# SCH_ultrasound_version2_2023-05-13.net
KiCad netlist of a schematic drawn in EasyEDA
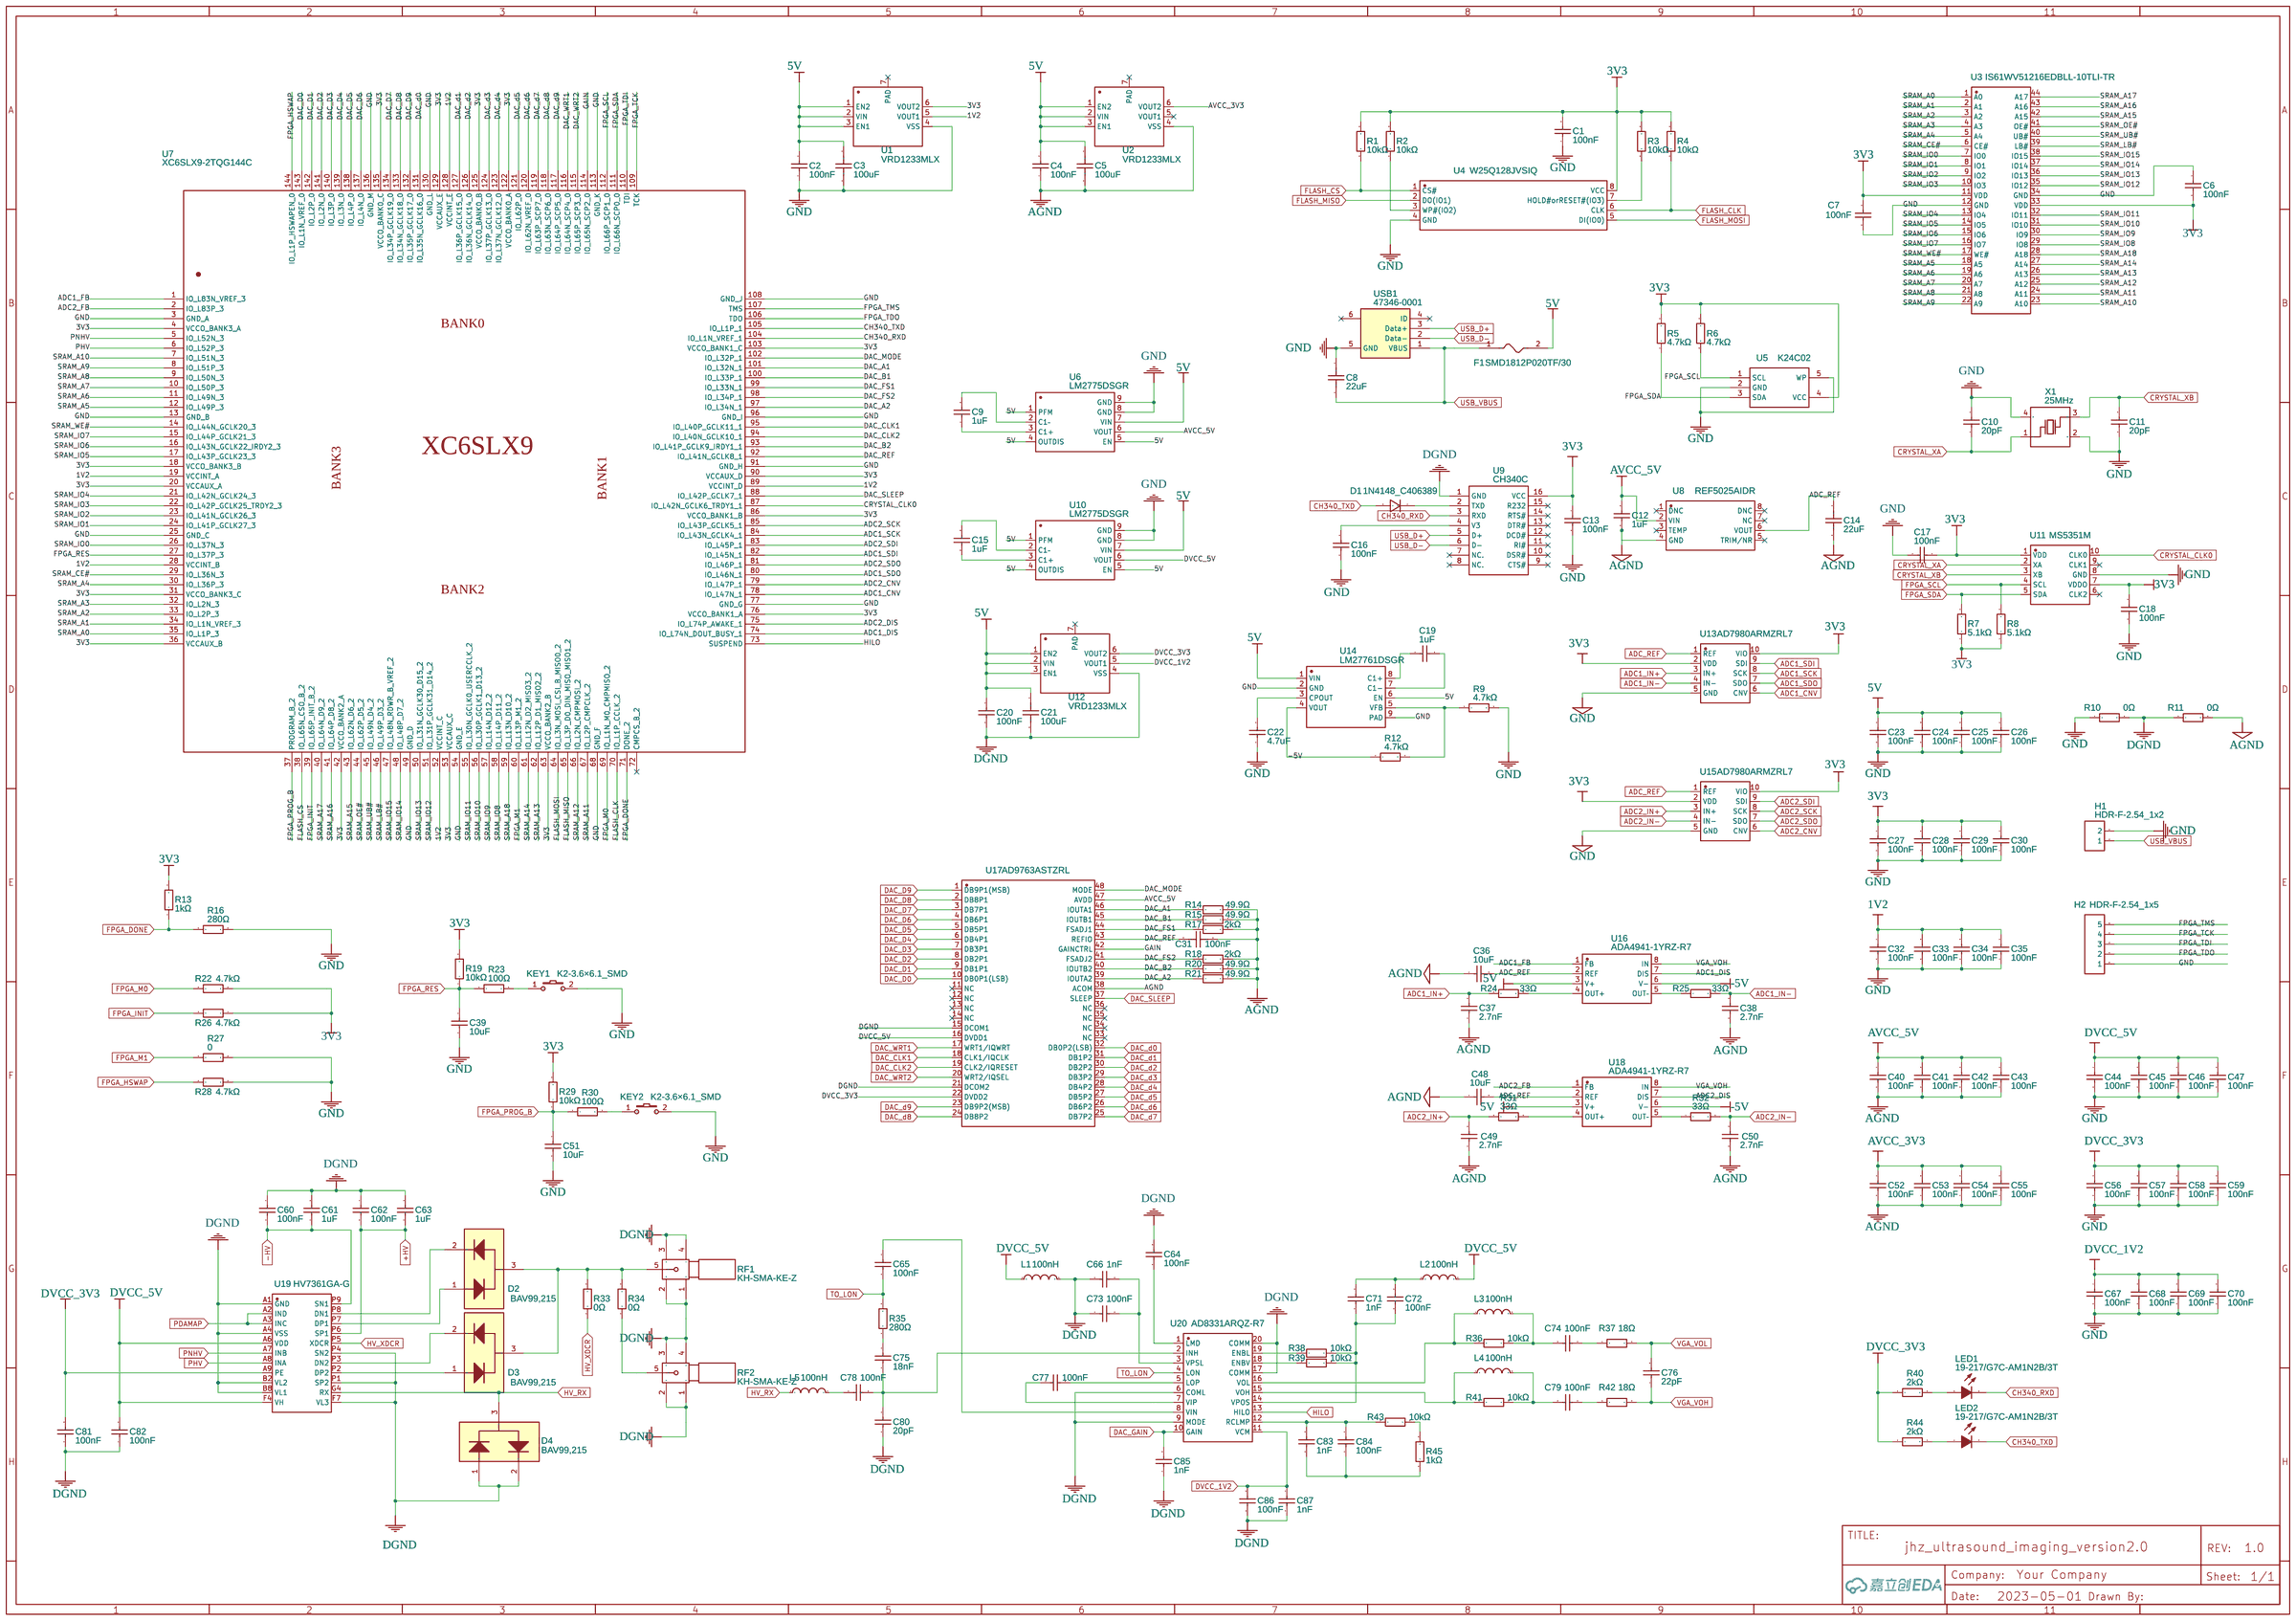
[diagram p0: schematic sheet]

(export (version "E")
  (design (tool "Eeschema 10.0.6"))
  (components
    (comp (ref "C1")
      (value "100nF")
      (fields
        (field (name "BOM_Manufacturer Part") "0603B104K500NT")
        (field (name "BOM_Supplier Part") "C30926")
      )
      (libsource (lib "") (part "0603B104K500NT"))
    )
    (comp (ref "C2")
      (value "100nF")
      (fields
        (field (name "BOM_Manufacturer Part") "0603B104K500NT")
        (field (name "BOM_Supplier Part") "C30926")
      )
      (libsource (lib "") (part "0603B104K500NT"))
    )
    (comp (ref "C3")
      (value "100uF")
      (fields
        (field (name "BOM_Manufacturer Part") "1206X107M6R3NT")
        (field (name "BOM_Supplier Part") "C178304")
      )
      (libsource (lib "") (part "1206X107M6R3NT"))
    )
    (comp (ref "C4")
      (value "100nF")
      (fields
        (field (name "BOM_Manufacturer Part") "0603B104K500NT")
        (field (name "BOM_Supplier Part") "C30926")
      )
      (libsource (lib "") (part "0603B104K500NT"))
    )
    (comp (ref "C5")
      (value "100uF")
      (fields
        (field (name "BOM_Manufacturer Part") "1206X107M6R3NT")
        (field (name "BOM_Supplier Part") "C178304")
      )
      (libsource (lib "") (part "1206X107M6R3NT"))
    )
    (comp (ref "C6")
      (value "100nF")
      (fields
        (field (name "BOM_Manufacturer Part") "0603B104K500NT")
        (field (name "BOM_Supplier Part") "C30926")
      )
      (libsource (lib "") (part "0603B104K500NT_1"))
    )
    (comp (ref "C7")
      (value "100nF")
      (fields
        (field (name "BOM_Manufacturer Part") "0603B104K500NT")
        (field (name "BOM_Supplier Part") "C30926")
      )
      (libsource (lib "") (part "0603B104K500NT"))
    )
    (comp (ref "C8")
      (value "22uF")
      (fields
        (field (name "BOM_Manufacturer Part") "0805X226M160NT")
        (field (name "BOM_Supplier Part") "C129302")
      )
      (libsource (lib "") (part "0805X226M160NT"))
    )
    (comp (ref "C9")
      (value "1uF")
      (fields
        (field (name "BOM_Manufacturer Part") "0603B105K250NT")
        (field (name "BOM_Supplier Part") "C59302")
      )
      (libsource (lib "") (part "0603B105K250NT"))
    )
    (comp (ref "C10")
      (value "20pF")
      (fields
        (field (name "BOM_Manufacturer Part") "0402CG200J500NT")
        (field (name "BOM_Supplier Part") "C1554")
      )
      (libsource (lib "") (part "0402CG200J500NT"))
    )
    (comp (ref "C11")
      (value "20pF")
      (fields
        (field (name "BOM_Manufacturer Part") "0402CG200J500NT")
        (field (name "BOM_Supplier Part") "C1554")
      )
      (libsource (lib "") (part "0402CG200J500NT"))
    )
    (comp (ref "C12")
      (value "1uF")
      (fields
        (field (name "BOM_Manufacturer Part") "0603B105K250NT")
        (field (name "BOM_Supplier Part") "C59302")
      )
      (libsource (lib "") (part "0603B105K250NT"))
    )
    (comp (ref "C13")
      (value "100nF")
      (fields
        (field (name "BOM_Manufacturer Part") "0603B104K500NT")
        (field (name "BOM_Supplier Part") "C30926")
      )
      (libsource (lib "") (part "0603B104K500NT_1"))
    )
    (comp (ref "C14")
      (value "22uF")
      (fields
        (field (name "BOM_Manufacturer Part") "0805X226M160NT")
        (field (name "BOM_Supplier Part") "C129302")
      )
      (libsource (lib "") (part "0805X226M160NT"))
    )
    (comp (ref "C15")
      (value "1uF")
      (fields
        (field (name "BOM_Manufacturer Part") "0603B105K250NT")
        (field (name "BOM_Supplier Part") "C59302")
      )
      (libsource (lib "") (part "0603B105K250NT"))
    )
    (comp (ref "C16")
      (value "100nF")
      (fields
        (field (name "BOM_Manufacturer Part") "0603B104K500NT")
        (field (name "BOM_Supplier Part") "C30926")
      )
      (libsource (lib "") (part "0603B104K500NT_1"))
    )
    (comp (ref "C17")
      (value "100nF")
      (fields
        (field (name "BOM_Manufacturer Part") "0603B104K500NT")
        (field (name "BOM_Supplier Part") "C30926")
      )
      (libsource (lib "") (part "0603B104K500NT_2"))
    )
    (comp (ref "C18")
      (value "100nF")
      (fields
        (field (name "BOM_Manufacturer Part") "0603B104K500NT")
        (field (name "BOM_Supplier Part") "C30926")
      )
      (libsource (lib "") (part "0603B104K500NT"))
    )
    (comp (ref "C19")
      (value "1uF")
      (fields
        (field (name "BOM_Manufacturer Part") "0603B105K250NT")
        (field (name "BOM_Supplier Part") "C59302")
      )
      (libsource (lib "") (part "0603B105K250NT_1"))
    )
    (comp (ref "C20")
      (value "100nF")
      (fields
        (field (name "BOM_Manufacturer Part") "0603B104K500NT")
        (field (name "BOM_Supplier Part") "C30926")
      )
      (libsource (lib "") (part "0603B104K500NT"))
    )
    (comp (ref "C21")
      (value "100uF")
      (fields
        (field (name "BOM_Manufacturer Part") "1206X107M6R3NT")
        (field (name "BOM_Supplier Part") "C178304")
      )
      (libsource (lib "") (part "1206X107M6R3NT"))
    )
    (comp (ref "C22")
      (value "4.7uF")
      (fields
        (field (name "BOM_Manufacturer Part") "1206B475K500NT")
        (field (name "BOM_Supplier Part") "C29823")
      )
      (libsource (lib "") (part "1206B475K500NT"))
    )
    (comp (ref "C23")
      (value "100nF")
      (fields
        (field (name "BOM_Manufacturer Part") "0603B104K500NT")
        (field (name "BOM_Supplier Part") "C30926")
      )
      (libsource (lib "") (part "0603B104K500NT_1"))
    )
    (comp (ref "C24")
      (value "100nF")
      (fields
        (field (name "BOM_Manufacturer Part") "0603B104K500NT")
        (field (name "BOM_Supplier Part") "C30926")
      )
      (libsource (lib "") (part "0603B104K500NT"))
    )
    (comp (ref "C25")
      (value "100nF")
      (fields
        (field (name "BOM_Manufacturer Part") "0603B104K500NT")
        (field (name "BOM_Supplier Part") "C30926")
      )
      (libsource (lib "") (part "0603B104K500NT"))
    )
    (comp (ref "C26")
      (value "100nF")
      (fields
        (field (name "BOM_Manufacturer Part") "0603B104K500NT")
        (field (name "BOM_Supplier Part") "C30926")
      )
      (libsource (lib "") (part "0603B104K500NT"))
    )
    (comp (ref "C27")
      (value "100nF")
      (fields
        (field (name "BOM_Manufacturer Part") "0603B104K500NT")
        (field (name "BOM_Supplier Part") "C30926")
      )
      (libsource (lib "") (part "0603B104K500NT_1"))
    )
    (comp (ref "C28")
      (value "100nF")
      (fields
        (field (name "BOM_Manufacturer Part") "0603B104K500NT")
        (field (name "BOM_Supplier Part") "C30926")
      )
      (libsource (lib "") (part "0603B104K500NT"))
    )
    (comp (ref "C29")
      (value "100nF")
      (fields
        (field (name "BOM_Manufacturer Part") "0603B104K500NT")
        (field (name "BOM_Supplier Part") "C30926")
      )
      (libsource (lib "") (part "0603B104K500NT"))
    )
    (comp (ref "C30")
      (value "100nF")
      (fields
        (field (name "BOM_Manufacturer Part") "0603B104K500NT")
        (field (name "BOM_Supplier Part") "C30926")
      )
      (libsource (lib "") (part "0603B104K500NT"))
    )
    (comp (ref "C31")
      (value "100nF")
      (fields
        (field (name "BOM_Manufacturer Part") "C0603B104K500NT")
        (field (name "BOM_Supplier Part") "C478888")
      )
      (libsource (lib "") (part "C0603B104K500NT"))
    )
    (comp (ref "C32")
      (value "100nF")
      (fields
        (field (name "BOM_Manufacturer Part") "0603B104K500NT")
        (field (name "BOM_Supplier Part") "C30926")
      )
      (libsource (lib "") (part "0603B104K500NT_1"))
    )
    (comp (ref "C33")
      (value "100nF")
      (fields
        (field (name "BOM_Manufacturer Part") "0603B104K500NT")
        (field (name "BOM_Supplier Part") "C30926")
      )
      (libsource (lib "") (part "0603B104K500NT"))
    )
    (comp (ref "C34")
      (value "100nF")
      (fields
        (field (name "BOM_Manufacturer Part") "0603B104K500NT")
        (field (name "BOM_Supplier Part") "C30926")
      )
      (libsource (lib "") (part "0603B104K500NT"))
    )
    (comp (ref "C35")
      (value "100nF")
      (fields
        (field (name "BOM_Manufacturer Part") "0603B104K500NT")
        (field (name "BOM_Supplier Part") "C30926")
      )
      (libsource (lib "") (part "0603B104K500NT"))
    )
    (comp (ref "C36")
      (value "10uF")
      (fields
        (field (name "BOM_Manufacturer Part") "0805X106K250NT")
        (field (name "BOM_Supplier Part") "C40894")
      )
      (libsource (lib "") (part "0805X106K250NT_1"))
    )
    (comp (ref "C37")
      (value "2.7nF")
      (fields
        (field (name "BOM_Manufacturer Part") "0603B272K500NT")
        (field (name "BOM_Supplier Part") "C1609")
      )
      (libsource (lib "") (part "0603B272K500NT"))
    )
    (comp (ref "C38")
      (value "2.7nF")
      (fields
        (field (name "BOM_Manufacturer Part") "0603B272K500NT")
        (field (name "BOM_Supplier Part") "C1609")
      )
      (libsource (lib "") (part "0603B272K500NT"))
    )
    (comp (ref "C39")
      (value "10uF")
      (fields
        (field (name "BOM_Manufacturer Part") "0805X106K250NT")
        (field (name "BOM_Supplier Part") "C40894")
      )
      (libsource (lib "") (part "0805X106K250NT"))
    )
    (comp (ref "C40")
      (value "100nF")
      (fields
        (field (name "BOM_Manufacturer Part") "0603B104K500NT")
        (field (name "BOM_Supplier Part") "C30926")
      )
      (libsource (lib "") (part "0603B104K500NT_1"))
    )
    (comp (ref "C41")
      (value "100nF")
      (fields
        (field (name "BOM_Manufacturer Part") "0603B104K500NT")
        (field (name "BOM_Supplier Part") "C30926")
      )
      (libsource (lib "") (part "0603B104K500NT"))
    )
    (comp (ref "C42")
      (value "100nF")
      (fields
        (field (name "BOM_Manufacturer Part") "0603B104K500NT")
        (field (name "BOM_Supplier Part") "C30926")
      )
      (libsource (lib "") (part "0603B104K500NT"))
    )
    (comp (ref "C43")
      (value "100nF")
      (fields
        (field (name "BOM_Manufacturer Part") "0603B104K500NT")
        (field (name "BOM_Supplier Part") "C30926")
      )
      (libsource (lib "") (part "0603B104K500NT"))
    )
    (comp (ref "C44")
      (value "100nF")
      (fields
        (field (name "BOM_Manufacturer Part") "0603B104K500NT")
        (field (name "BOM_Supplier Part") "C30926")
      )
      (libsource (lib "") (part "0603B104K500NT_1"))
    )
    (comp (ref "C45")
      (value "100nF")
      (fields
        (field (name "BOM_Manufacturer Part") "0603B104K500NT")
        (field (name "BOM_Supplier Part") "C30926")
      )
      (libsource (lib "") (part "0603B104K500NT"))
    )
    (comp (ref "C46")
      (value "100nF")
      (fields
        (field (name "BOM_Manufacturer Part") "0603B104K500NT")
        (field (name "BOM_Supplier Part") "C30926")
      )
      (libsource (lib "") (part "0603B104K500NT"))
    )
    (comp (ref "C47")
      (value "100nF")
      (fields
        (field (name "BOM_Manufacturer Part") "0603B104K500NT")
        (field (name "BOM_Supplier Part") "C30926")
      )
      (libsource (lib "") (part "0603B104K500NT"))
    )
    (comp (ref "C48")
      (value "10uF")
      (fields
        (field (name "BOM_Manufacturer Part") "0805X106K250NT")
        (field (name "BOM_Supplier Part") "C40894")
      )
      (libsource (lib "") (part "0805X106K250NT_1"))
    )
    (comp (ref "C49")
      (value "2.7nF")
      (fields
        (field (name "BOM_Manufacturer Part") "0603B272K500NT")
        (field (name "BOM_Supplier Part") "C1609")
      )
      (libsource (lib "") (part "0603B272K500NT"))
    )
    (comp (ref "C50")
      (value "2.7nF")
      (fields
        (field (name "BOM_Manufacturer Part") "0603B272K500NT")
        (field (name "BOM_Supplier Part") "C1609")
      )
      (libsource (lib "") (part "0603B272K500NT"))
    )
    (comp (ref "C51")
      (value "10uF")
      (fields
        (field (name "BOM_Manufacturer Part") "0805X106K250NT")
        (field (name "BOM_Supplier Part") "C40894")
      )
      (libsource (lib "") (part "0805X106K250NT"))
    )
    (comp (ref "C52")
      (value "100nF")
      (fields
        (field (name "BOM_Manufacturer Part") "0603B104K500NT")
        (field (name "BOM_Supplier Part") "C30926")
      )
      (libsource (lib "") (part "0603B104K500NT_1"))
    )
    (comp (ref "C53")
      (value "100nF")
      (fields
        (field (name "BOM_Manufacturer Part") "0603B104K500NT")
        (field (name "BOM_Supplier Part") "C30926")
      )
      (libsource (lib "") (part "0603B104K500NT"))
    )
    (comp (ref "C54")
      (value "100nF")
      (fields
        (field (name "BOM_Manufacturer Part") "0603B104K500NT")
        (field (name "BOM_Supplier Part") "C30926")
      )
      (libsource (lib "") (part "0603B104K500NT"))
    )
    (comp (ref "C55")
      (value "100nF")
      (fields
        (field (name "BOM_Manufacturer Part") "0603B104K500NT")
        (field (name "BOM_Supplier Part") "C30926")
      )
      (libsource (lib "") (part "0603B104K500NT"))
    )
    (comp (ref "C56")
      (value "100nF")
      (fields
        (field (name "BOM_Manufacturer Part") "0603B104K500NT")
        (field (name "BOM_Supplier Part") "C30926")
      )
      (libsource (lib "") (part "0603B104K500NT_1"))
    )
    (comp (ref "C57")
      (value "100nF")
      (fields
        (field (name "BOM_Manufacturer Part") "0603B104K500NT")
        (field (name "BOM_Supplier Part") "C30926")
      )
      (libsource (lib "") (part "0603B104K500NT"))
    )
    (comp (ref "C58")
      (value "100nF")
      (fields
        (field (name "BOM_Manufacturer Part") "0603B104K500NT")
        (field (name "BOM_Supplier Part") "C30926")
      )
      (libsource (lib "") (part "0603B104K500NT"))
    )
    (comp (ref "C59")
      (value "100nF")
      (fields
        (field (name "BOM_Manufacturer Part") "0603B104K500NT")
        (field (name "BOM_Supplier Part") "C30926")
      )
      (libsource (lib "") (part "0603B104K500NT"))
    )
    (comp (ref "C60")
      (value "100nF")
      (fields
        (field (name "BOM_Manufacturer Part") "0603B104K500NT")
        (field (name "BOM_Supplier Part") "C30926")
      )
      (libsource (lib "") (part "0603B104K500NT_1"))
    )
    (comp (ref "C61")
      (value "1uF")
      (fields
        (field (name "BOM_Manufacturer Part") "0603B105K250NT")
        (field (name "BOM_Supplier Part") "C59302")
      )
      (libsource (lib "") (part "0603B105K250NT"))
    )
    (comp (ref "C62")
      (value "100nF")
      (fields
        (field (name "BOM_Manufacturer Part") "0603B104K500NT")
        (field (name "BOM_Supplier Part") "C30926")
      )
      (libsource (lib "") (part "0603B104K500NT_1"))
    )
    (comp (ref "C63")
      (value "1uF")
      (fields
        (field (name "BOM_Manufacturer Part") "0603B105K250NT")
        (field (name "BOM_Supplier Part") "C59302")
      )
      (libsource (lib "") (part "0603B105K250NT"))
    )
    (comp (ref "C64")
      (value "100nF")
      (fields
        (field (name "BOM_Manufacturer Part") "0603B104K500NT")
        (field (name "BOM_Supplier Part") "C30926")
      )
      (libsource (lib "") (part "0603B104K500NT"))
    )
    (comp (ref "C65")
      (value "100nF")
      (fields
        (field (name "BOM_Manufacturer Part") "0603B104K500NT")
        (field (name "BOM_Supplier Part") "C30926")
      )
      (libsource (lib "") (part "0603B104K500NT"))
    )
    (comp (ref "C66")
      (value "1nF")
      (fields
        (field (name "BOM_Manufacturer Part") "1206B102K202NT")
        (field (name "BOM_Supplier Part") "C9196")
      )
      (libsource (lib "") (part "1206B102K202NT_1"))
    )
    (comp (ref "C67")
      (value "100nF")
      (fields
        (field (name "BOM_Manufacturer Part") "0603B104K500NT")
        (field (name "BOM_Supplier Part") "C30926")
      )
      (libsource (lib "") (part "0603B104K500NT_1"))
    )
    (comp (ref "C68")
      (value "100nF")
      (fields
        (field (name "BOM_Manufacturer Part") "0603B104K500NT")
        (field (name "BOM_Supplier Part") "C30926")
      )
      (libsource (lib "") (part "0603B104K500NT"))
    )
    (comp (ref "C69")
      (value "100nF")
      (fields
        (field (name "BOM_Manufacturer Part") "0603B104K500NT")
        (field (name "BOM_Supplier Part") "C30926")
      )
      (libsource (lib "") (part "0603B104K500NT"))
    )
    (comp (ref "C70")
      (value "100nF")
      (fields
        (field (name "BOM_Manufacturer Part") "0603B104K500NT")
        (field (name "BOM_Supplier Part") "C30926")
      )
      (libsource (lib "") (part "0603B104K500NT"))
    )
    (comp (ref "C71")
      (value "1nF")
      (fields
        (field (name "BOM_Manufacturer Part") "1206B102K202NT")
        (field (name "BOM_Supplier Part") "C9196")
      )
      (libsource (lib "") (part "1206B102K202NT"))
    )
    (comp (ref "C72")
      (value "100nF")
      (fields
        (field (name "BOM_Manufacturer Part") "0603B104K500NT")
        (field (name "BOM_Supplier Part") "C30926")
      )
      (libsource (lib "") (part "0603B104K500NT"))
    )
    (comp (ref "C73")
      (value "100nF")
      (fields
        (field (name "BOM_Manufacturer Part") "0603B104K500NT")
        (field (name "BOM_Supplier Part") "C30926")
      )
      (libsource (lib "") (part "0603B104K500NT_2"))
    )
    (comp (ref "C74")
      (value "100nF")
      (fields
        (field (name "BOM_Manufacturer Part") "0603B104K500NT")
        (field (name "BOM_Supplier Part") "C30926")
      )
      (libsource (lib "") (part "0603B104K500NT_3"))
    )
    (comp (ref "C75")
      (value "18nF")
      (fields
        (field (name "BOM_Manufacturer Part") "0805B183K500NT")
        (field (name "BOM_Supplier Part") "C1723")
      )
      (libsource (lib "") (part "0805B183K500NT"))
    )
    (comp (ref "C76")
      (value "22pF")
      (fields
        (field (name "BOM_Manufacturer Part") "0402CG220J500NT")
        (field (name "BOM_Supplier Part") "C1555")
      )
      (libsource (lib "") (part "0402CG220J500NT"))
    )
    (comp (ref "C77")
      (value "100nF")
      (fields
        (field (name "BOM_Manufacturer Part") "0603B104K500NT")
        (field (name "BOM_Supplier Part") "C30926")
      )
      (libsource (lib "") (part "0603B104K500NT_2"))
    )
    (comp (ref "C78")
      (value "100nF")
      (fields
        (field (name "BOM_Manufacturer Part") "0603B104K500NT")
        (field (name "BOM_Supplier Part") "C30926")
      )
      (libsource (lib "") (part "0603B104K500NT_2"))
    )
    (comp (ref "C79")
      (value "100nF")
      (fields
        (field (name "BOM_Manufacturer Part") "0603B104K500NT")
        (field (name "BOM_Supplier Part") "C30926")
      )
      (libsource (lib "") (part "0603B104K500NT_3"))
    )
    (comp (ref "C80")
      (value "20pF")
      (fields
        (field (name "BOM_Manufacturer Part") "0402CG200J500NT")
        (field (name "BOM_Supplier Part") "C1554")
      )
      (libsource (lib "") (part "0402CG200J500NT"))
    )
    (comp (ref "C81")
      (value "100nF")
      (fields
        (field (name "BOM_Manufacturer Part") "0603B104K500NT")
        (field (name "BOM_Supplier Part") "C30926")
      )
      (libsource (lib "") (part "0603B104K500NT"))
    )
    (comp (ref "C82")
      (value "100nF")
      (fields
        (field (name "BOM_Manufacturer Part") "0603B104K500NT")
        (field (name "BOM_Supplier Part") "C30926")
      )
      (libsource (lib "") (part "0603B104K500NT"))
    )
    (comp (ref "C83")
      (value "1nF")
      (fields
        (field (name "BOM_Manufacturer Part") "1206B102K202NT")
        (field (name "BOM_Supplier Part") "C9196")
      )
      (libsource (lib "") (part "1206B102K202NT"))
    )
    (comp (ref "C84")
      (value "100nF")
      (fields
        (field (name "BOM_Manufacturer Part") "0603B104K500NT")
        (field (name "BOM_Supplier Part") "C30926")
      )
      (libsource (lib "") (part "0603B104K500NT"))
    )
    (comp (ref "C85")
      (value "1nF")
      (fields
        (field (name "BOM_Manufacturer Part") "1206B102K202NT")
        (field (name "BOM_Supplier Part") "C9196")
      )
      (libsource (lib "") (part "1206B102K202NT"))
    )
    (comp (ref "C86")
      (value "100nF")
      (fields
        (field (name "BOM_Manufacturer Part") "0603B104K500NT")
        (field (name "BOM_Supplier Part") "C30926")
      )
      (libsource (lib "") (part "0603B104K500NT_1"))
    )
    (comp (ref "C87")
      (value "1nF")
      (fields
        (field (name "BOM_Manufacturer Part") "1206B102K202NT")
        (field (name "BOM_Supplier Part") "C9196")
      )
      (libsource (lib "") (part "1206B102K202NT_2"))
    )
    (comp (ref "D1")
      (value "1N4148_C406389")
      (fields (field (name "BOM_Manufacturer Part") "1N4148") (field (name "BOM_Supplier Part") "C406389"))
      (libsource (lib "") (part "1N4148_C406389"))
    )
    (comp (ref "D2")
      (value "BAV99,215")
      (fields (field (name "BOM_Supplier Part") "C2500"))
      (libsource (lib "") (part "BAV99,215"))
    )
    (comp (ref "D3")
      (value "BAV99,215")
      (fields (field (name "BOM_Supplier Part") "C2500"))
      (libsource (lib "") (part "BAV99,215"))
    )
    (comp (ref "D4")
      (value "BAV99,215")
      (fields (field (name "BOM_Supplier Part") "C2500"))
      (libsource (lib "") (part "BAV99,215_1"))
    )
    (comp (ref "F1")
      (value "SMD1812P020TF/30")
      (fields (field (name "BOM_Supplier Part") "C13575"))
      (libsource (lib "") (part "SMD1812P020TF/30"))
    )
    (comp (ref "H1")
      (value "HDR-F-2.54_1x2")
      (fields (field (name "BOM_Supplier Part") "C49661"))
      (libsource (lib "") (part "HDR-F-2.54_1x2"))
    )
    (comp (ref "H2")
      (value "HDR-F-2.54_1x5")
      (fields (field (name "BOM_Supplier Part") "C50950"))
      (libsource (lib "") (part "HDR-F-2.54_1x5"))
    )
    (comp (ref "KEY1")
      (value "K2-3.6×6.1_SMD")
      (fields
        (field (name "BOM_Manufacturer Part") "K2-1107ST-A4SW-06")
        (field (name "BOM_Supplier Part") "C118141")
      )
      (libsource (lib "") (part "K2-3.6×6.1_SMD"))
    )
    (comp (ref "KEY2")
      (value "K2-3.6×6.1_SMD")
      (fields
        (field (name "BOM_Manufacturer Part") "K2-1107ST-A4SW-06")
        (field (name "BOM_Supplier Part") "C118141")
      )
      (libsource (lib "") (part "K2-3.6×6.1_SMD"))
    )
    (comp (ref "L1")
      (value "100nH")
      (fields
        (field (name "BOM_Manufacturer Part") "VHF160808HR10JT")
        (field (name "BOM_Supplier Part") "C90214")
      )
      (libsource (lib "") (part "VHF160808HR10JT"))
    )
    (comp (ref "L2")
      (value "100nH")
      (fields
        (field (name "BOM_Manufacturer Part") "VHF160808HR10JT")
        (field (name "BOM_Supplier Part") "C90214")
      )
      (libsource (lib "") (part "VHF160808HR10JT"))
    )
    (comp (ref "L3")
      (value "100nH")
      (fields
        (field (name "BOM_Manufacturer Part") "VHF160808HR10JT")
        (field (name "BOM_Supplier Part") "C90214")
      )
      (libsource (lib "") (part "VHF160808HR10JT"))
    )
    (comp (ref "L4")
      (value "100nH")
      (fields
        (field (name "BOM_Manufacturer Part") "VHF160808HR10JT")
        (field (name "BOM_Supplier Part") "C90214")
      )
      (libsource (lib "") (part "VHF160808HR10JT"))
    )
    (comp (ref "L5")
      (value "100nH")
      (fields
        (field (name "BOM_Manufacturer Part") "VHF160808HR10JT")
        (field (name "BOM_Supplier Part") "C90214")
      )
      (libsource (lib "") (part "VHF160808HR10JT_1"))
    )
    (comp (ref "LED1")
      (value "19-217/G7C-AM1N2B/3T")
      (fields (field (name "BOM_Supplier Part") "C183844"))
      (libsource (lib "") (part "19-217/G7C-AM1N2B/3T"))
    )
    (comp (ref "LED2")
      (value "19-217/G7C-AM1N2B/3T")
      (fields (field (name "BOM_Supplier Part") "C183844"))
      (libsource (lib "") (part "19-217/G7C-AM1N2B/3T"))
    )
    (comp (ref "R1")
      (value "10kΩ")
      (fields
        (field (name "BOM_Manufacturer Part") "RS-03K1002FT")
        (field (name "BOM_Supplier Part") "C115324")
      )
      (libsource (lib "") (part "RS-03K1002FT_1"))
    )
    (comp (ref "R2")
      (value "10kΩ")
      (fields
        (field (name "BOM_Manufacturer Part") "RS-03K1002FT")
        (field (name "BOM_Supplier Part") "C115324")
      )
      (libsource (lib "") (part "RS-03K1002FT_1"))
    )
    (comp (ref "R3")
      (value "10kΩ")
      (fields
        (field (name "BOM_Manufacturer Part") "RS-03K1002FT")
        (field (name "BOM_Supplier Part") "C115324")
      )
      (libsource (lib "") (part "RS-03K1002FT_1"))
    )
    (comp (ref "R4")
      (value "10kΩ")
      (fields
        (field (name "BOM_Manufacturer Part") "RS-03K1002FT")
        (field (name "BOM_Supplier Part") "C115324")
      )
      (libsource (lib "") (part "RS-03K1002FT_1"))
    )
    (comp (ref "R5")
      (value "4.7kΩ")
      (fields
        (field (name "BOM_Manufacturer Part") "RS-03K4701FT")
        (field (name "BOM_Supplier Part") "C116693")
      )
      (libsource (lib "") (part "RS-03K4701FT_2"))
    )
    (comp (ref "R6")
      (value "4.7kΩ")
      (fields
        (field (name "BOM_Manufacturer Part") "RS-03K4701FT")
        (field (name "BOM_Supplier Part") "C116693")
      )
      (libsource (lib "") (part "RS-03K4701FT_2"))
    )
    (comp (ref "R7")
      (value "5.1kΩ")
      (fields
        (field (name "BOM_Manufacturer Part") "RS-03K5101FT")
        (field (name "BOM_Supplier Part") "C156350")
      )
      (libsource (lib "") (part "RS-03K5101FT"))
    )
    (comp (ref "R8")
      (value "5.1kΩ")
      (fields
        (field (name "BOM_Manufacturer Part") "RS-03K5101FT")
        (field (name "BOM_Supplier Part") "C156350")
      )
      (libsource (lib "") (part "RS-03K5101FT"))
    )
    (comp (ref "R9")
      (value "4.7kΩ")
      (fields
        (field (name "BOM_Manufacturer Part") "RS-03K4701FT")
        (field (name "BOM_Supplier Part") "C116693")
      )
      (libsource (lib "") (part "RS-03K4701FT_1"))
    )
    (comp (ref "R10")
      (value "0Ω")
      (fields
        (field (name "BOM_Manufacturer Part") "RS-03000JT")
        (field (name "BOM_Supplier Part") "C115304")
      )
      (libsource (lib "") (part "RS-03000JT_C115304_1"))
    )
    (comp (ref "R11")
      (value "0Ω")
      (fields
        (field (name "BOM_Manufacturer Part") "RS-03000JT")
        (field (name "BOM_Supplier Part") "C115304")
      )
      (libsource (lib "") (part "RS-03000JT_C115304_1"))
    )
    (comp (ref "R12")
      (value "4.7kΩ")
      (fields
        (field (name "BOM_Manufacturer Part") "RS-03K4701FT")
        (field (name "BOM_Supplier Part") "C116693")
      )
      (libsource (lib "") (part "RS-03K4701FT_1"))
    )
    (comp (ref "R13")
      (value "1kΩ")
      (fields
        (field (name "BOM_Manufacturer Part") "RS-03K1001FT")
        (field (name "BOM_Supplier Part") "C115325")
      )
      (libsource (lib "") (part "RS-03K1001FT"))
    )
    (comp (ref "R14")
      (value "49.9Ω")
      (fields
        (field (name "BOM_Manufacturer Part") "RC-02W49R9FT")
        (field (name "BOM_Supplier Part") "C258106")
      )
      (libsource (lib "") (part "RC-02W49R9FT"))
    )
    (comp (ref "R15")
      (value "49.9Ω")
      (fields
        (field (name "BOM_Manufacturer Part") "RC-02W49R9FT")
        (field (name "BOM_Supplier Part") "C258106")
      )
      (libsource (lib "") (part "RC-02W49R9FT"))
    )
    (comp (ref "R16")
      (value "280Ω")
      (fields
        (field (name "BOM_Manufacturer Part") "RC-02W2800FT")
        (field (name "BOM_Supplier Part") "C321421")
      )
      (libsource (lib "") (part "RC-02W2800FT"))
    )
    (comp (ref "R17")
      (value "2kΩ")
      (fields
        (field (name "BOM_Manufacturer Part") "RS-03K2001FT")
        (field (name "BOM_Supplier Part") "C115336")
      )
      (libsource (lib "") (part "RS-03K2001FT"))
    )
    (comp (ref "R18")
      (value "2kΩ")
      (fields
        (field (name "BOM_Manufacturer Part") "RS-03K2001FT")
        (field (name "BOM_Supplier Part") "C115336")
      )
      (libsource (lib "") (part "RS-03K2001FT"))
    )
    (comp (ref "R19")
      (value "10kΩ")
      (fields
        (field (name "BOM_Manufacturer Part") "RS-03K1002FT")
        (field (name "BOM_Supplier Part") "C115324")
      )
      (libsource (lib "") (part "RS-03K1002FT_1"))
    )
    (comp (ref "R20")
      (value "49.9Ω")
      (fields
        (field (name "BOM_Manufacturer Part") "RC-02W49R9FT")
        (field (name "BOM_Supplier Part") "C258106")
      )
      (libsource (lib "") (part "RC-02W49R9FT"))
    )
    (comp (ref "R21")
      (value "49.9Ω")
      (fields
        (field (name "BOM_Manufacturer Part") "RC-02W49R9FT")
        (field (name "BOM_Supplier Part") "C258106")
      )
      (libsource (lib "") (part "RC-02W49R9FT"))
    )
    (comp (ref "R22")
      (value "4.7kΩ")
      (fields
        (field (name "BOM_Manufacturer Part") "RS-03K4701FT")
        (field (name "BOM_Supplier Part") "C116693")
      )
      (libsource (lib "") (part "RS-03K4701FT_1"))
    )
    (comp (ref "R23")
      (value "100Ω")
      (fields
        (field (name "BOM_Manufacturer Part") "RS-03K101JT")
        (field (name "BOM_Supplier Part") "C86983")
      )
      (libsource (lib "") (part "RS-03K101JT"))
    )
    (comp (ref "R24")
      (value "33Ω")
      (fields
        (field (name "BOM_Manufacturer Part") "RC-02W33R0FT")
        (field (name "BOM_Supplier Part") "C140161")
      )
      (libsource (lib "") (part "RC-02W33R0FT"))
    )
    (comp (ref "R25")
      (value "33Ω")
      (fields
        (field (name "BOM_Manufacturer Part") "RC-02W33R0FT")
        (field (name "BOM_Supplier Part") "C140161")
      )
      (libsource (lib "") (part "RC-02W33R0FT"))
    )
    (comp (ref "R26")
      (value "4.7kΩ")
      (fields
        (field (name "BOM_Manufacturer Part") "RS-03K4701FT")
        (field (name "BOM_Supplier Part") "C116693")
      )
      (libsource (lib "") (part "RS-03K4701FT"))
    )
    (comp (ref "R27")
      (value "0")
      (fields (field (name "BOM_Manufacturer Part") "RS-03000JT") (field (name "BOM_Supplier Part") "C73810"))
      (libsource (lib "") (part "RS-03000JT"))
    )
    (comp (ref "R28")
      (value "4.7kΩ")
      (fields
        (field (name "BOM_Manufacturer Part") "RS-03K4701FT")
        (field (name "BOM_Supplier Part") "C116693")
      )
      (libsource (lib "") (part "RS-03K4701FT"))
    )
    (comp (ref "R29")
      (value "10kΩ")
      (fields
        (field (name "BOM_Manufacturer Part") "RS-03K1002FT")
        (field (name "BOM_Supplier Part") "C115324")
      )
      (libsource (lib "") (part "RS-03K1002FT_1"))
    )
    (comp (ref "R30")
      (value "100Ω")
      (fields
        (field (name "BOM_Manufacturer Part") "RS-03K101JT")
        (field (name "BOM_Supplier Part") "C86983")
      )
      (libsource (lib "") (part "RS-03K101JT"))
    )
    (comp (ref "R31")
      (value "33Ω")
      (fields
        (field (name "BOM_Manufacturer Part") "RC-02W33R0FT")
        (field (name "BOM_Supplier Part") "C140161")
      )
      (libsource (lib "") (part "RC-02W33R0FT"))
    )
    (comp (ref "R32")
      (value "33Ω")
      (fields
        (field (name "BOM_Manufacturer Part") "RC-02W33R0FT")
        (field (name "BOM_Supplier Part") "C140161")
      )
      (libsource (lib "") (part "RC-02W33R0FT"))
    )
    (comp (ref "R33")
      (value "0Ω")
      (fields
        (field (name "BOM_Manufacturer Part") "RS-03000JT")
        (field (name "BOM_Supplier Part") "C115304")
      )
      (libsource (lib "") (part "RS-03000JT_C115304"))
    )
    (comp (ref "R34")
      (value "0Ω")
      (fields
        (field (name "BOM_Manufacturer Part") "RS-03000JT")
        (field (name "BOM_Supplier Part") "C115304")
      )
      (libsource (lib "") (part "RS-03000JT_C115304"))
    )
    (comp (ref "R35")
      (value "280Ω")
      (fields
        (field (name "BOM_Manufacturer Part") "RC-02W2800FT")
        (field (name "BOM_Supplier Part") "C321421")
      )
      (libsource (lib "") (part "RC-02W2800FT_1"))
    )
    (comp (ref "R36")
      (value "10kΩ")
      (fields
        (field (name "BOM_Manufacturer Part") "RS-03K1002FT")
        (field (name "BOM_Supplier Part") "C115324")
      )
      (libsource (lib "") (part "RS-03K1002FT"))
    )
    (comp (ref "R37")
      (value "18Ω")
      (fields
        (field (name "BOM_Manufacturer Part") "RS-03K180JT")
        (field (name "BOM_Supplier Part") "C286576")
      )
      (libsource (lib "") (part "RS-03K180JT"))
    )
    (comp (ref "R38")
      (value "10kΩ")
      (fields
        (field (name "BOM_Manufacturer Part") "RS-03K1002FT")
        (field (name "BOM_Supplier Part") "C115324")
      )
      (libsource (lib "") (part "RS-03K1002FT"))
    )
    (comp (ref "R39")
      (value "10kΩ")
      (fields
        (field (name "BOM_Manufacturer Part") "RS-03K1002FT")
        (field (name "BOM_Supplier Part") "C115324")
      )
      (libsource (lib "") (part "RS-03K1002FT"))
    )
    (comp (ref "R40")
      (value "2kΩ")
      (fields
        (field (name "BOM_Manufacturer Part") "RS-03K2001FT")
        (field (name "BOM_Supplier Part") "C115336")
      )
      (libsource (lib "") (part "RS-03K2001FT"))
    )
    (comp (ref "R41")
      (value "10kΩ")
      (fields
        (field (name "BOM_Manufacturer Part") "RS-03K1002FT")
        (field (name "BOM_Supplier Part") "C115324")
      )
      (libsource (lib "") (part "RS-03K1002FT"))
    )
    (comp (ref "R42")
      (value "18Ω")
      (fields
        (field (name "BOM_Manufacturer Part") "RS-03K180JT")
        (field (name "BOM_Supplier Part") "C286576")
      )
      (libsource (lib "") (part "RS-03K180JT"))
    )
    (comp (ref "R43")
      (value "10kΩ")
      (fields
        (field (name "BOM_Manufacturer Part") "RS-03K1002FT")
        (field (name "BOM_Supplier Part") "C115324")
      )
      (libsource (lib "") (part "RS-03K1002FT"))
    )
    (comp (ref "R44")
      (value "2kΩ")
      (fields
        (field (name "BOM_Manufacturer Part") "RS-03K2001FT")
        (field (name "BOM_Supplier Part") "C115336")
      )
      (libsource (lib "") (part "RS-03K2001FT"))
    )
    (comp (ref "R45")
      (value "1kΩ")
      (fields
        (field (name "BOM_Manufacturer Part") "RS-03K1001FT")
        (field (name "BOM_Supplier Part") "C115325")
      )
      (libsource (lib "") (part "RS-03K1001FT"))
    )
    (comp (ref "RF1")
      (value "KH-SMA-KE-Z")
      (fields (field (name "BOM_Supplier Part") "C504007"))
      (libsource (lib "") (part "KH-SMA-KE-Z"))
    )
    (comp (ref "RF2")
      (value "KH-SMA-KE-Z")
      (fields (field (name "BOM_Supplier Part") "C504007"))
      (libsource (lib "") (part "KH-SMA-KE-Z"))
    )
    (comp (ref "U1")
      (value "VRD1233MLX")
      (fields (field (name "BOM_Supplier Part") "C697903"))
      (libsource (lib "") (part "VRD1233MLX"))
    )
    (comp (ref "U2")
      (value "VRD1233MLX")
      (fields (field (name "BOM_Supplier Part") "C697903"))
      (libsource (lib "") (part "VRD1233MLX"))
    )
    (comp (ref "U3")
      (value "IS61WV51216EDBLL-10TLI-TR")
      (fields (field (name "BOM_Supplier Part") "C2065273"))
      (libsource (lib "") (part "IS61WV51216EDBLL-10TLI-TR"))
    )
    (comp (ref "U4")
      (value "W25Q128JVSIQ")
      (fields (field (name "BOM_Supplier Part") "C113767"))
      (libsource (lib "") (part "W25Q128JVSIQ"))
    )
    (comp (ref "U5")
      (value "K24C02")
      (fields (field (name "BOM_Supplier Part") "C84964"))
      (libsource (lib "") (part "K24C02"))
    )
    (comp (ref "U6")
      (value "LM2775DSGR")
      (fields (field (name "BOM_Supplier Part") "C473361"))
      (libsource (lib "") (part "LM2775DSGR"))
    )
    (comp (ref "U7")
      (value "XC6SLX9-2TQG144C")
      (fields (field (name "BOM_Supplier Part") "C27408"))
      (libsource (lib "") (part "XC6SLX9-2TQG144C"))
    )
    (comp (ref "U8")
      (value "REF5025AIDR")
      (fields (field (name "BOM_Supplier Part") "C11341"))
      (libsource (lib "") (part "REF5025AIDR"))
    )
    (comp (ref "U9")
      (value "CH340C")
      (fields (field (name "BOM_Supplier Part") "C84681"))
      (libsource (lib "") (part "CH340C"))
    )
    (comp (ref "U10")
      (value "LM2775DSGR")
      (fields (field (name "BOM_Supplier Part") "C473361"))
      (libsource (lib "") (part "LM2775DSGR"))
    )
    (comp (ref "U11")
      (value "MS5351M")
      (fields (field (name "BOM_Supplier Part") "C1509083"))
      (libsource (lib "") (part "MS5351M"))
    )
    (comp (ref "U12")
      (value "VRD1233MLX")
      (fields (field (name "BOM_Supplier Part") "C697903"))
      (libsource (lib "") (part "VRD1233MLX"))
    )
    (comp (ref "U13")
      (value "AD7980ARMZRL7")
      (fields (field (name "BOM_Supplier Part") "C578576"))
      (libsource (lib "") (part "AD7980ARMZRL7"))
    )
    (comp (ref "U14")
      (value "LM27761DSGR")
      (fields (field (name "BOM_Supplier Part") "C129351"))
      (libsource (lib "") (part "LM27761DSGR"))
    )
    (comp (ref "U15")
      (value "AD7980ARMZRL7")
      (fields (field (name "BOM_Supplier Part") "C578576"))
      (libsource (lib "") (part "AD7980ARMZRL7"))
    )
    (comp (ref "U16")
      (value "ADA4941-1YRZ-R7")
      (fields (field (name "BOM_Supplier Part") "C495334"))
      (libsource (lib "") (part "ADA4941-1YRZ-R7"))
    )
    (comp (ref "U17")
      (value "AD9763ASTZRL")
      (fields (field (name "BOM_Supplier Part") "C481891"))
      (libsource (lib "") (part "AD9763ASTZRL"))
    )
    (comp (ref "U18")
      (value "ADA4941-1YRZ-R7")
      (fields (field (name "BOM_Supplier Part") "C495334"))
      (libsource (lib "") (part "ADA4941-1YRZ-R7"))
    )
    (comp (ref "U19")
      (value "HV7361GA-G")
      (fields (field (name "BOM_Supplier Part") "C633420"))
      (libsource (lib "") (part "HV7361GA-G"))
    )
    (comp (ref "U20")
      (value "AD8331ARQZ-R7")
      (fields (field (name "BOM_Supplier Part") "C578697"))
      (libsource (lib "") (part "AD8331ARQZ-R7"))
    )
    (comp (ref "USB1")
      (value "47346-0001")
      (fields (field (name "BOM_Manufacturer Part") "473460001") (field (name "BOM_Supplier Part") "C132560"))
      (libsource (lib "") (part "47346-0001"))
    )
    (comp (ref "X1")
      (value "25MHz")
      (fields
        (field (name "BOM_Manufacturer Part") "X322525MOB4SI")
        (field (name "BOM_Supplier Part") "C9006")
      )
      (libsource (lib "") (part "X322525MOB4SI"))
    )
  )
  (nets
    (net (code "1") (name "+HV") (class "Default")
      (node (ref "C62") (pin "2") (pinfunction "2_2") (pintype "input"))
      (node (ref "C63") (pin "1") (pinfunction "1_1") (pintype "input"))
      (node (ref "U19") (pin "P6") (pinfunction "SP1_P6") (pintype "unspecified"))
    )
    (net (code "2") (name "-5V") (class "Default")
      (node (ref "R12") (pin "1") (pinfunction "1_1") (pintype "unspecified"))
      (node (ref "U14") (pin "4") (pinfunction "VOUT_4") (pintype "unspecified"))
      (node (ref "U16") (pin "6") (pinfunction "V-_6") (pintype "unspecified"))
      (node (ref "U18") (pin "6") (pinfunction "V-_6") (pintype "unspecified"))
    )
    (net (code "3") (name "-HV") (class "Default")
      (node (ref "C60") (pin "2") (pinfunction "2_2") (pintype "input"))
      (node (ref "C61") (pin "1") (pinfunction "1_1") (pintype "input"))
      (node (ref "U19") (pin "P9") (pinfunction "SN1_P9") (pintype "unspecified"))
    )
    (net (code "4") (name "/ADC1_DIS") (class "Default")
      (node (ref "U16") (pin "7") (pinfunction "DIS_7") (pintype "unspecified"))
      (node (ref "U7") (pin "74") (pinfunction "IO_L74N_DOUT_BUSY_1_74") (pintype "unspecified"))
    )
    (net (code "5") (name "/ADC1_FB") (class "Default")
      (node (ref "U16") (pin "1") (pinfunction "FB_1") (pintype "unspecified"))
      (node (ref "U7") (pin "1") (pinfunction "IO_L83N_VREF_3_1") (pintype "unspecified"))
    )
    (net (code "6") (name "/ADC2_DIS") (class "Default")
      (node (ref "U18") (pin "7") (pinfunction "DIS_7") (pintype "unspecified"))
      (node (ref "U7") (pin "75") (pinfunction "IO_L74P_AWAKE_1_75") (pintype "unspecified"))
    )
    (net (code "7") (name "/ADC2_FB") (class "Default")
      (node (ref "U18") (pin "1") (pinfunction "FB_1") (pintype "unspecified"))
      (node (ref "U7") (pin "2") (pinfunction "IO_L83P_3_2") (pintype "unspecified"))
    )
    (net (code "8") (name "/DAC_A1") (class "Default")
      (node (ref "R14") (pin "1") (pinfunction "1_1") (pintype "unspecified"))
      (node (ref "U17") (pin "46") (pinfunction "IOUTA1_46") (pintype "unspecified"))
      (node (ref "U7") (pin "101") (pinfunction "IO_L32N_1_101") (pintype "unspecified"))
    )
    (net (code "9") (name "/DAC_A2") (class "Default")
      (node (ref "R21") (pin "1") (pinfunction "1_1") (pintype "unspecified"))
      (node (ref "U17") (pin "39") (pinfunction "IOUTA2_39") (pintype "unspecified"))
      (node (ref "U7") (pin "97") (pinfunction "IO_L34N_1_97") (pintype "unspecified"))
    )
    (net (code "10") (name "/DAC_B1") (class "Default")
      (node (ref "R15") (pin "1") (pinfunction "1_1") (pintype "unspecified"))
      (node (ref "U17") (pin "45") (pinfunction "IOUTB1_45") (pintype "unspecified"))
      (node (ref "U7") (pin "100") (pinfunction "IO_L33P_1_100") (pintype "unspecified"))
    )
    (net (code "11") (name "/DAC_B2") (class "Default")
      (node (ref "R20") (pin "1") (pinfunction "1_1") (pintype "unspecified"))
      (node (ref "U17") (pin "40") (pinfunction "IOUTB2_40") (pintype "unspecified"))
      (node (ref "U7") (pin "93") (pinfunction "IO_L41P_GCLK9_IRDY1_1_93") (pintype "unspecified"))
    )
    (net (code "12") (name "/DAC_FS1") (class "Default")
      (node (ref "R17") (pin "1") (pinfunction "1_1") (pintype "input"))
      (node (ref "U17") (pin "44") (pinfunction "FSADJ1_44") (pintype "unspecified"))
      (node (ref "U7") (pin "99") (pinfunction "IO_L33N_1_99") (pintype "unspecified"))
    )
    (net (code "13") (name "/DAC_FS2") (class "Default")
      (node (ref "R18") (pin "1") (pinfunction "1_1") (pintype "input"))
      (node (ref "U17") (pin "41") (pinfunction "FSADJ2_41") (pintype "unspecified"))
      (node (ref "U7") (pin "98") (pinfunction "IO_L34P_1_98") (pintype "unspecified"))
    )
    (net (code "14") (name "/DAC_MODE") (class "Default")
      (node (ref "U17") (pin "48") (pinfunction "MODE_48") (pintype "unspecified"))
      (node (ref "U7") (pin "102") (pinfunction "IO_L32P_1_102") (pintype "unspecified"))
    )
    (net (code "15") (name "/DAC_REF") (class "Default")
      (node (ref "C31") (pin "1") (pinfunction "1_1") (pintype "unspecified"))
      (node (ref "U17") (pin "43") (pinfunction "REFIO_43") (pintype "unspecified"))
      (node (ref "U7") (pin "92") (pinfunction "IO_L41N_GCLK8_1_92") (pintype "unspecified"))
    )
    (net (code "16") (name "/FPGA_TCK") (class "Default")
      (node (ref "H2") (pin "4") (pinfunction "4_4") (pintype "unspecified"))
      (node (ref "U7") (pin "109") (pinfunction "TCK_109") (pintype "unspecified"))
    )
    (net (code "17") (name "/FPGA_TDI") (class "Default")
      (node (ref "H2") (pin "3") (pinfunction "3_3") (pintype "unspecified"))
      (node (ref "U7") (pin "110") (pinfunction "TDI_110") (pintype "unspecified"))
    )
    (net (code "18") (name "/FPGA_TDO") (class "Default")
      (node (ref "H2") (pin "2") (pinfunction "2_2") (pintype "unspecified"))
      (node (ref "U7") (pin "106") (pinfunction "TDO_106") (pintype "unspecified"))
    )
    (net (code "19") (name "/FPGA_TMS") (class "Default")
      (node (ref "H2") (pin "5") (pinfunction "5_5") (pintype "unspecified"))
      (node (ref "U7") (pin "107") (pinfunction "TMS_107") (pintype "unspecified"))
    )
    (net (code "20") (name "/GAIN") (class "Default")
      (node (ref "U17") (pin "42") (pinfunction "GAINCTRL_42") (pintype "unspecified"))
      (node (ref "U7") (pin "114") (pinfunction "IO_L65N_SCP2_0_114") (pintype "unspecified"))
    )
    (net (code "21") (name "/SRAM_A0") (class "Default")
      (node (ref "U3") (pin "1") (pinfunction "A0_1") (pintype "unspecified"))
      (node (ref "U7") (pin "35") (pinfunction "IO_L1P_3_35") (pintype "unspecified"))
    )
    (net (code "22") (name "/SRAM_A1") (class "Default")
      (node (ref "U3") (pin "2") (pinfunction "A1_2") (pintype "unspecified"))
      (node (ref "U7") (pin "34") (pinfunction "IO_L1N_VREF_3_34") (pintype "unspecified"))
    )
    (net (code "23") (name "/SRAM_A2") (class "Default")
      (node (ref "U3") (pin "3") (pinfunction "A2_3") (pintype "unspecified"))
      (node (ref "U7") (pin "33") (pinfunction "IO_L2P_3_33") (pintype "unspecified"))
    )
    (net (code "24") (name "/SRAM_A3") (class "Default")
      (node (ref "U3") (pin "4") (pinfunction "A3_4") (pintype "unspecified"))
      (node (ref "U7") (pin "32") (pinfunction "IO_L2N_3_32") (pintype "unspecified"))
    )
    (net (code "25") (name "/SRAM_A4") (class "Default")
      (node (ref "U3") (pin "5") (pinfunction "A4_5") (pintype "unspecified"))
      (node (ref "U7") (pin "30") (pinfunction "IO_L36P_3_30") (pintype "unspecified"))
    )
    (net (code "26") (name "/SRAM_A5") (class "Default")
      (node (ref "U3") (pin "18") (pinfunction "A5_18") (pintype "unspecified"))
      (node (ref "U7") (pin "12") (pinfunction "IO_L49P_3_12") (pintype "unspecified"))
    )
    (net (code "27") (name "/SRAM_A6") (class "Default")
      (node (ref "U3") (pin "19") (pinfunction "A6_19") (pintype "unspecified"))
      (node (ref "U7") (pin "11") (pinfunction "IO_L49N_3_11") (pintype "unspecified"))
    )
    (net (code "28") (name "/SRAM_A7") (class "Default")
      (node (ref "U3") (pin "20") (pinfunction "A7_20") (pintype "unspecified"))
      (node (ref "U7") (pin "10") (pinfunction "IO_L50P_3_10") (pintype "unspecified"))
    )
    (net (code "29") (name "/SRAM_A8") (class "Default")
      (node (ref "U3") (pin "21") (pinfunction "A8_21") (pintype "unspecified"))
      (node (ref "U7") (pin "9") (pinfunction "IO_L50N_3_9") (pintype "unspecified"))
    )
    (net (code "30") (name "/SRAM_A9") (class "Default")
      (node (ref "U3") (pin "22") (pinfunction "A9_22") (pintype "unspecified"))
      (node (ref "U7") (pin "8") (pinfunction "IO_L51P_3_8") (pintype "unspecified"))
    )
    (net (code "31") (name "/SRAM_A10") (class "Default")
      (node (ref "U3") (pin "23") (pinfunction "A10_23") (pintype "unspecified"))
      (node (ref "U7") (pin "7") (pinfunction "IO_L51N_3_7") (pintype "unspecified"))
    )
    (net (code "32") (name "/SRAM_A11") (class "Default")
      (node (ref "U3") (pin "24") (pinfunction "A11_24") (pintype "unspecified"))
      (node (ref "U7") (pin "67") (pinfunction "IO_L2P_CMPCLK_2_67") (pintype "unspecified"))
    )
    (net (code "33") (name "/SRAM_A12") (class "Default")
      (node (ref "U3") (pin "25") (pinfunction "A12_25") (pintype "unspecified"))
      (node (ref "U7") (pin "66") (pinfunction "IO_L2N_CMPMOSI_2_66") (pintype "unspecified"))
    )
    (net (code "34") (name "/SRAM_A13") (class "Default")
      (node (ref "U3") (pin "26") (pinfunction "A13_26") (pintype "unspecified"))
      (node (ref "U7") (pin "62") (pinfunction "IO_L12P_D1_MISO2_2_62") (pintype "unspecified"))
    )
    (net (code "35") (name "/SRAM_A14") (class "Default")
      (node (ref "U3") (pin "27") (pinfunction "A14_27") (pintype "unspecified"))
      (node (ref "U7") (pin "61") (pinfunction "IO_L12N_D2_MISO3_2_61") (pintype "unspecified"))
    )
    (net (code "36") (name "/SRAM_A15") (class "Default")
      (node (ref "U3") (pin "42") (pinfunction "A15_42") (pintype "unspecified"))
      (node (ref "U7") (pin "43") (pinfunction "IO_L62N_D6_2_43") (pintype "unspecified"))
    )
    (net (code "37") (name "/SRAM_A16") (class "Default")
      (node (ref "U3") (pin "43") (pinfunction "A16_43") (pintype "unspecified"))
      (node (ref "U7") (pin "41") (pinfunction "IO_L64P_D8_2_41") (pintype "unspecified"))
    )
    (net (code "38") (name "/SRAM_A17") (class "Default")
      (node (ref "U3") (pin "44") (pinfunction "A17_44") (pintype "unspecified"))
      (node (ref "U7") (pin "40") (pinfunction "IO_L64N_D9_2_40") (pintype "unspecified"))
    )
    (net (code "39") (name "/SRAM_A18") (class "Default")
      (node (ref "U3") (pin "28") (pinfunction "A18_28") (pintype "unspecified"))
      (node (ref "U7") (pin "59") (pinfunction "IO_L13N_D10_2_59") (pintype "unspecified"))
    )
    (net (code "40") (name "/SRAM_CE#") (class "Default")
      (node (ref "U3") (pin "6") (pinfunction "CE#_6") (pintype "unspecified"))
      (node (ref "U7") (pin "29") (pinfunction "IO_L36N_3_29") (pintype "unspecified"))
    )
    (net (code "41") (name "/SRAM_IO0") (class "Default")
      (node (ref "U3") (pin "7") (pinfunction "IO0_7") (pintype "unspecified"))
      (node (ref "U7") (pin "26") (pinfunction "IO_L37N_3_26") (pintype "unspecified"))
    )
    (net (code "42") (name "/SRAM_IO1") (class "Default")
      (node (ref "U3") (pin "8") (pinfunction "IO1_8") (pintype "unspecified"))
      (node (ref "U7") (pin "24") (pinfunction "IO_L41P_GCLK27_3_24") (pintype "unspecified"))
    )
    (net (code "43") (name "/SRAM_IO2") (class "Default")
      (node (ref "U3") (pin "9") (pinfunction "IO2_9") (pintype "unspecified"))
      (node (ref "U7") (pin "23") (pinfunction "IO_L41N_GCLK26_3_23") (pintype "unspecified"))
    )
    (net (code "44") (name "/SRAM_IO3") (class "Default")
      (node (ref "U3") (pin "10") (pinfunction "IO3_10") (pintype "unspecified"))
      (node (ref "U7") (pin "22") (pinfunction "IO_L42P_GCLK25_TRDY2_3_22") (pintype "unspecified"))
    )
    (net (code "45") (name "/SRAM_IO4") (class "Default")
      (node (ref "U3") (pin "13") (pinfunction "IO4_13") (pintype "unspecified"))
      (node (ref "U7") (pin "21") (pinfunction "IO_L42N_GCLK24_3_21") (pintype "unspecified"))
    )
    (net (code "46") (name "/SRAM_IO5") (class "Default")
      (node (ref "U3") (pin "14") (pinfunction "IO5_14") (pintype "unspecified"))
      (node (ref "U7") (pin "17") (pinfunction "IO_L43P_GCLK23_3_17") (pintype "unspecified"))
    )
    (net (code "47") (name "/SRAM_IO6") (class "Default")
      (node (ref "U3") (pin "15") (pinfunction "IO6_15") (pintype "unspecified"))
      (node (ref "U7") (pin "16") (pinfunction "IO_L43N_GCLK22_IRDY2_3_16") (pintype "unspecified"))
    )
    (net (code "48") (name "/SRAM_IO7") (class "Default")
      (node (ref "U3") (pin "16") (pinfunction "IO7_16") (pintype "unspecified"))
      (node (ref "U7") (pin "15") (pinfunction "IO_L44P_GCLK21_3_15") (pintype "unspecified"))
    )
    (net (code "49") (name "/SRAM_IO8") (class "Default")
      (node (ref "U3") (pin "29") (pinfunction "IO8_29") (pintype "unspecified"))
      (node (ref "U7") (pin "58") (pinfunction "IO_L14P_D11_2_58") (pintype "unspecified"))
    )
    (net (code "50") (name "/SRAM_IO9") (class "Default")
      (node (ref "U3") (pin "30") (pinfunction "IO9_30") (pintype "unspecified"))
      (node (ref "U7") (pin "57") (pinfunction "IO_L14N_D12_2_57") (pintype "unspecified"))
    )
    (net (code "51") (name "/SRAM_IO10") (class "Default")
      (node (ref "U3") (pin "31") (pinfunction "IO10_31") (pintype "unspecified"))
      (node (ref "U7") (pin "56") (pinfunction "IO_L30P_GCLK1_D13_2_56") (pintype "unspecified"))
    )
    (net (code "52") (name "/SRAM_IO11") (class "Default")
      (node (ref "U3") (pin "32") (pinfunction "IO11_32") (pintype "unspecified"))
      (node (ref "U7") (pin "55") (pinfunction "IO_L30N_GCLK0_USERCCLK_2_55") (pintype "unspecified"))
    )
    (net (code "53") (name "/SRAM_IO12") (class "Default")
      (node (ref "U3") (pin "35") (pinfunction "IO12_35") (pintype "unspecified"))
      (node (ref "U7") (pin "51") (pinfunction "IO_L31P_GCLK31_D14_2_51") (pintype "unspecified"))
    )
    (net (code "54") (name "/SRAM_IO13") (class "Default")
      (node (ref "U3") (pin "36") (pinfunction "IO13_36") (pintype "unspecified"))
      (node (ref "U7") (pin "50") (pinfunction "IO_L31N_GCLK30_D15_2_50") (pintype "unspecified"))
    )
    (net (code "55") (name "/SRAM_IO14") (class "Default")
      (node (ref "U3") (pin "37") (pinfunction "IO14_37") (pintype "unspecified"))
      (node (ref "U7") (pin "48") (pinfunction "IO_L48P_D7_2_48") (pintype "unspecified"))
    )
    (net (code "56") (name "/SRAM_IO15") (class "Default")
      (node (ref "U3") (pin "38") (pinfunction "IO15_38") (pintype "unspecified"))
      (node (ref "U7") (pin "47") (pinfunction "IO_L48N_RDWR_B_VREF_2_47") (pintype "unspecified"))
    )
    (net (code "57") (name "/SRAM_LB#") (class "Default")
      (node (ref "U3") (pin "39") (pinfunction "LB#_39") (pintype "unspecified"))
      (node (ref "U7") (pin "46") (pinfunction "IO_L49P_D3_2_46") (pintype "unspecified"))
    )
    (net (code "58") (name "/SRAM_OE#") (class "Default")
      (node (ref "U3") (pin "41") (pinfunction "OE#_41") (pintype "unspecified"))
      (node (ref "U7") (pin "44") (pinfunction "IO_L62P_D5_2_44") (pintype "unspecified"))
    )
    (net (code "59") (name "/SRAM_UB#") (class "Default")
      (node (ref "U3") (pin "40") (pinfunction "UB#_40") (pintype "unspecified"))
      (node (ref "U7") (pin "45") (pinfunction "IO_L49N_D4_2_45") (pintype "unspecified"))
    )
    (net (code "60") (name "/SRAM_WE#") (class "Default")
      (node (ref "U3") (pin "17") (pinfunction "WE#_17") (pintype "unspecified"))
      (node (ref "U7") (pin "14") (pinfunction "IO_L44N_GCLK20_3_14") (pintype "unspecified"))
    )
    (net (code "61") (name "1V2") (class "Default")
      (node (ref "C32") (pin "1") (pinfunction "1_1") (pintype "input"))
      (node (ref "C33") (pin "2") (pinfunction "2_2") (pintype "input"))
      (node (ref "C34") (pin "2") (pinfunction "2_2") (pintype "input"))
      (node (ref "C35") (pin "2") (pinfunction "2_2") (pintype "input"))
      (node (ref "U1") (pin "5") (pinfunction "VOUT1_5") (pintype "unspecified"))
      (node (ref "U7") (pin "128") (pinfunction "VCCINT_E_128") (pintype "passive"))
      (node (ref "U7") (pin "19") (pinfunction "VCCINT_A_19") (pintype "passive"))
      (node (ref "U7") (pin "28") (pinfunction "VCCINT_B_28") (pintype "passive"))
      (node (ref "U7") (pin "52") (pinfunction "VCCINT_C_52") (pintype "passive"))
      (node (ref "U7") (pin "89") (pinfunction "VCCINT_D_89") (pintype "passive"))
    )
    (net (code "62") (name "3V3") (class "Default")
      (node (ref "C1") (pin "2") (pinfunction "2_2") (pintype "input"))
      (node (ref "C13") (pin "1") (pinfunction "1_1") (pintype "input"))
      (node (ref "C17") (pin "2") (pinfunction "2_2") (pintype "input"))
      (node (ref "C18") (pin "2") (pinfunction "2_2") (pintype "input"))
      (node (ref "C27") (pin "1") (pinfunction "1_1") (pintype "input"))
      (node (ref "C28") (pin "2") (pinfunction "2_2") (pintype "input"))
      (node (ref "C29") (pin "2") (pinfunction "2_2") (pintype "input"))
      (node (ref "C30") (pin "2") (pinfunction "2_2") (pintype "input"))
      (node (ref "C6") (pin "2") (pinfunction "2_2") (pintype "input"))
      (node (ref "C7") (pin "2") (pinfunction "2_2") (pintype "input"))
      (node (ref "R1") (pin "2") (pinfunction "2_2") (pintype "unspecified"))
      (node (ref "R13") (pin "2") (pinfunction "2_2") (pintype "input"))
      (node (ref "R19") (pin "2") (pinfunction "2_2") (pintype "unspecified"))
      (node (ref "R2") (pin "2") (pinfunction "2_2") (pintype "unspecified"))
      (node (ref "R22") (pin "2") (pinfunction "2_2") (pintype "unspecified"))
      (node (ref "R26") (pin "1") (pinfunction "1_1") (pintype "unspecified"))
      (node (ref "R29") (pin "2") (pinfunction "2_2") (pintype "unspecified"))
      (node (ref "R3") (pin "2") (pinfunction "2_2") (pintype "unspecified"))
      (node (ref "R4") (pin "2") (pinfunction "2_2") (pintype "unspecified"))
      (node (ref "R5") (pin "2") (pinfunction "2_2") (pintype "unspecified"))
      (node (ref "R6") (pin "2") (pinfunction "2_2") (pintype "unspecified"))
      (node (ref "R7") (pin "1") (pinfunction "1_1") (pintype "unspecified"))
      (node (ref "R8") (pin "1") (pinfunction "1_1") (pintype "unspecified"))
      (node (ref "U1") (pin "6") (pinfunction "VOUT2_6") (pintype "unspecified"))
      (node (ref "U11") (pin "1") (pinfunction "VDD_1") (pintype "unspecified"))
      (node (ref "U11") (pin "7") (pinfunction "VDDO_7") (pintype "unspecified"))
      (node (ref "U13") (pin "10") (pinfunction "VIO_10") (pintype "unspecified"))
      (node (ref "U13") (pin "2") (pinfunction "VDD_2") (pintype "unspecified"))
      (node (ref "U15") (pin "10") (pinfunction "VIO_10") (pintype "unspecified"))
      (node (ref "U15") (pin "2") (pinfunction "VDD_2") (pintype "unspecified"))
      (node (ref "U3") (pin "11") (pinfunction "VDD_11") (pintype "unspecified"))
      (node (ref "U3") (pin "33") (pinfunction "VDD_33") (pintype "unspecified"))
      (node (ref "U4") (pin "8") (pinfunction "VCC_8") (pintype "unspecified"))
      (node (ref "U5") (pin "4") (pinfunction "VCC_4") (pintype "unspecified"))
      (node (ref "U7") (pin "103") (pinfunction "VCCO_BANK1_C_103") (pintype "passive"))
      (node (ref "U7") (pin "122") (pinfunction "VCCO_BANK0_A_122") (pintype "passive"))
      (node (ref "U7") (pin "125") (pinfunction "VCCO_BANK0_B_125") (pintype "passive"))
      (node (ref "U7") (pin "129") (pinfunction "VCCAUX_E_129") (pintype "passive"))
      (node (ref "U7") (pin "135") (pinfunction "VCCO_BANK0_C_135") (pintype "passive"))
      (node (ref "U7") (pin "18") (pinfunction "VCCO_BANK3_B_18") (pintype "passive"))
      (node (ref "U7") (pin "20") (pinfunction "VCCAUX_A_20") (pintype "passive"))
      (node (ref "U7") (pin "31") (pinfunction "VCCO_BANK3_C_31") (pintype "passive"))
      (node (ref "U7") (pin "36") (pinfunction "VCCAUX_B_36") (pintype "passive"))
      (node (ref "U7") (pin "4") (pinfunction "VCCO_BANK3_A_4") (pintype "passive"))
      (node (ref "U7") (pin "42") (pinfunction "VCCO_BANK2_A_42") (pintype "passive"))
      (node (ref "U7") (pin "53") (pinfunction "VCCAUX_C_53") (pintype "passive"))
      (node (ref "U7") (pin "63") (pinfunction "VCCO_BANK2_B_63") (pintype "passive"))
      (node (ref "U7") (pin "76") (pinfunction "VCCO_BANK1_A_76") (pintype "passive"))
      (node (ref "U7") (pin "86") (pinfunction "VCCO_BANK1_B_86") (pintype "passive"))
      (node (ref "U7") (pin "90") (pinfunction "VCCAUX_D_90") (pintype "passive"))
      (node (ref "U9") (pin "16") (pinfunction "VCC_16") (pintype "unspecified"))
    )
    (net (code "63") (name "5V") (class "Default")
      (node (ref "C2") (pin "2") (pinfunction "2_2") (pintype "input"))
      (node (ref "C20") (pin "2") (pinfunction "2_2") (pintype "input"))
      (node (ref "C21") (pin "1") (pinfunction "1_1") (pintype "unspecified"))
      (node (ref "C23") (pin "1") (pinfunction "1_1") (pintype "input"))
      (node (ref "C24") (pin "2") (pinfunction "2_2") (pintype "input"))
      (node (ref "C25") (pin "2") (pinfunction "2_2") (pintype "input"))
      (node (ref "C26") (pin "2") (pinfunction "2_2") (pintype "input"))
      (node (ref "C3") (pin "1") (pinfunction "1_1") (pintype "unspecified"))
      (node (ref "C4") (pin "2") (pinfunction "2_2") (pintype "input"))
      (node (ref "C5") (pin "1") (pinfunction "1_1") (pintype "unspecified"))
      (node (ref "F1") (pin "2") (pinfunction "2_2") (pintype "unspecified"))
      (node (ref "U1") (pin "1") (pinfunction "EN2_1") (pintype "unspecified"))
      (node (ref "U1") (pin "2") (pinfunction "VIN_2") (pintype "unspecified"))
      (node (ref "U1") (pin "3") (pinfunction "EN1_3") (pintype "unspecified"))
      (node (ref "U10") (pin "1") (pinfunction "PFM_1") (pintype "unspecified"))
      (node (ref "U10") (pin "4") (pinfunction "OUTDIS_4") (pintype "unspecified"))
      (node (ref "U10") (pin "5") (pinfunction "EN_5") (pintype "unspecified"))
      (node (ref "U10") (pin "7") (pinfunction "VIN_7") (pintype "unspecified"))
      (node (ref "U12") (pin "1") (pinfunction "EN2_1") (pintype "unspecified"))
      (node (ref "U12") (pin "2") (pinfunction "VIN_2") (pintype "unspecified"))
      (node (ref "U12") (pin "3") (pinfunction "EN1_3") (pintype "unspecified"))
      (node (ref "U14") (pin "1") (pinfunction "VIN_1") (pintype "unspecified"))
      (node (ref "U14") (pin "6") (pinfunction "EN_6") (pintype "unspecified"))
      (node (ref "U16") (pin "3") (pinfunction "V+_3") (pintype "unspecified"))
      (node (ref "U18") (pin "3") (pinfunction "V+_3") (pintype "unspecified"))
      (node (ref "U2") (pin "1") (pinfunction "EN2_1") (pintype "unspecified"))
      (node (ref "U2") (pin "2") (pinfunction "VIN_2") (pintype "unspecified"))
      (node (ref "U2") (pin "3") (pinfunction "EN1_3") (pintype "unspecified"))
      (node (ref "U6") (pin "1") (pinfunction "PFM_1") (pintype "unspecified"))
      (node (ref "U6") (pin "4") (pinfunction "OUTDIS_4") (pintype "unspecified"))
      (node (ref "U6") (pin "5") (pinfunction "EN_5") (pintype "unspecified"))
      (node (ref "U6") (pin "7") (pinfunction "VIN_7") (pintype "unspecified"))
    )
    (net (code "64") (name "ADC1_CNV") (class "Default")
      (node (ref "U13") (pin "6") (pinfunction "CNV_6") (pintype "unspecified"))
      (node (ref "U7") (pin "78") (pinfunction "IO_L47N_1_78") (pintype "unspecified"))
    )
    (net (code "65") (name "ADC1_IN+") (class "Default")
      (node (ref "C37") (pin "2") (pinfunction "2_2") (pintype "input"))
      (node (ref "R24") (pin "1") (pinfunction "1_1") (pintype "unspecified"))
      (node (ref "U13") (pin "3") (pinfunction "IN+_3") (pintype "unspecified"))
    )
    (net (code "66") (name "ADC1_IN-") (class "Default")
      (node (ref "C38") (pin "2") (pinfunction "2_2") (pintype "input"))
      (node (ref "R25") (pin "2") (pinfunction "2_2") (pintype "unspecified"))
      (node (ref "U13") (pin "4") (pinfunction "IN-_4") (pintype "unspecified"))
    )
    (net (code "67") (name "ADC1_SCK") (class "Default")
      (node (ref "U13") (pin "8") (pinfunction "SCK_8") (pintype "unspecified"))
      (node (ref "U7") (pin "84") (pinfunction "IO_L43N_GCLK4_1_84") (pintype "unspecified"))
    )
    (net (code "68") (name "ADC1_SDI") (class "Default")
      (node (ref "U13") (pin "9") (pinfunction "SDI_9") (pintype "unspecified"))
      (node (ref "U7") (pin "82") (pinfunction "IO_L45N_1_82") (pintype "unspecified"))
    )
    (net (code "69") (name "ADC1_SDO") (class "Default")
      (node (ref "U13") (pin "7") (pinfunction "SDO_7") (pintype "unspecified"))
      (node (ref "U7") (pin "80") (pinfunction "IO_L46N_1_80") (pintype "unspecified"))
    )
    (net (code "70") (name "ADC2_CNV") (class "Default")
      (node (ref "U15") (pin "6") (pinfunction "CNV_6") (pintype "unspecified"))
      (node (ref "U7") (pin "79") (pinfunction "IO_L47P_1_79") (pintype "unspecified"))
    )
    (net (code "71") (name "ADC2_IN+") (class "Default")
      (node (ref "C49") (pin "2") (pinfunction "2_2") (pintype "input"))
      (node (ref "R31") (pin "1") (pinfunction "1_1") (pintype "unspecified"))
      (node (ref "U15") (pin "3") (pinfunction "IN+_3") (pintype "unspecified"))
    )
    (net (code "72") (name "ADC2_IN-") (class "Default")
      (node (ref "C50") (pin "2") (pinfunction "2_2") (pintype "input"))
      (node (ref "R32") (pin "2") (pinfunction "2_2") (pintype "unspecified"))
      (node (ref "U15") (pin "4") (pinfunction "IN-_4") (pintype "unspecified"))
    )
    (net (code "73") (name "ADC2_SCK") (class "Default")
      (node (ref "U15") (pin "8") (pinfunction "SCK_8") (pintype "unspecified"))
      (node (ref "U7") (pin "85") (pinfunction "IO_L43P_GCLK5_1_85") (pintype "unspecified"))
    )
    (net (code "74") (name "ADC2_SDI") (class "Default")
      (node (ref "U15") (pin "9") (pinfunction "SDI_9") (pintype "unspecified"))
      (node (ref "U7") (pin "83") (pinfunction "IO_L45P_1_83") (pintype "unspecified"))
    )
    (net (code "75") (name "ADC2_SDO") (class "Default")
      (node (ref "U15") (pin "7") (pinfunction "SDO_7") (pintype "unspecified"))
      (node (ref "U7") (pin "81") (pinfunction "IO_L46P_1_81") (pintype "unspecified"))
    )
    (net (code "76") (name "ADC_REF") (class "Default")
      (node (ref "C14") (pin "1") (pinfunction "1_1") (pintype "unspecified"))
      (node (ref "C36") (pin "2") (pinfunction "2_2") (pintype "input"))
      (node (ref "C48") (pin "2") (pinfunction "2_2") (pintype "input"))
      (node (ref "U13") (pin "1") (pinfunction "REF_1") (pintype "unspecified"))
      (node (ref "U15") (pin "1") (pinfunction "REF_1") (pintype "unspecified"))
      (node (ref "U16") (pin "2") (pinfunction "REF_2") (pintype "unspecified"))
      (node (ref "U18") (pin "2") (pinfunction "REF_2") (pintype "unspecified"))
      (node (ref "U8") (pin "6") (pinfunction "VOUT_6") (pintype "unspecified"))
    )
    (net (code "77") (name "AGND") (class "Default")
      (node (ref "C12") (pin "1") (pinfunction "1_1") (pintype "input"))
      (node (ref "C14") (pin "2") (pinfunction "2_2") (pintype "unspecified"))
      (node (ref "C31") (pin "2") (pinfunction "2_2") (pintype "unspecified"))
      (node (ref "C36") (pin "1") (pinfunction "1_1") (pintype "input"))
      (node (ref "C37") (pin "1") (pinfunction "1_1") (pintype "input"))
      (node (ref "C38") (pin "1") (pinfunction "1_1") (pintype "input"))
      (node (ref "C4") (pin "1") (pinfunction "1_1") (pintype "input"))
      (node (ref "C40") (pin "2") (pinfunction "2_2") (pintype "input"))
      (node (ref "C41") (pin "1") (pinfunction "1_1") (pintype "input"))
      (node (ref "C42") (pin "1") (pinfunction "1_1") (pintype "input"))
      (node (ref "C43") (pin "1") (pinfunction "1_1") (pintype "input"))
      (node (ref "C48") (pin "1") (pinfunction "1_1") (pintype "input"))
      (node (ref "C49") (pin "1") (pinfunction "1_1") (pintype "input"))
      (node (ref "C5") (pin "2") (pinfunction "2_2") (pintype "unspecified"))
      (node (ref "C50") (pin "1") (pinfunction "1_1") (pintype "input"))
      (node (ref "C52") (pin "2") (pinfunction "2_2") (pintype "input"))
      (node (ref "C53") (pin "1") (pinfunction "1_1") (pintype "input"))
      (node (ref "C54") (pin "1") (pinfunction "1_1") (pintype "input"))
      (node (ref "C55") (pin "1") (pinfunction "1_1") (pintype "input"))
      (node (ref "R11") (pin "2") (pinfunction "2_2") (pintype "unspecified"))
      (node (ref "R14") (pin "2") (pinfunction "2_2") (pintype "unspecified"))
      (node (ref "R15") (pin "2") (pinfunction "2_2") (pintype "unspecified"))
      (node (ref "R17") (pin "2") (pinfunction "2_2") (pintype "input"))
      (node (ref "R18") (pin "2") (pinfunction "2_2") (pintype "input"))
      (node (ref "R20") (pin "2") (pinfunction "2_2") (pintype "unspecified"))
      (node (ref "R21") (pin "2") (pinfunction "2_2") (pintype "unspecified"))
      (node (ref "U17") (pin "38") (pinfunction "ACOM_38") (pintype "unspecified"))
      (node (ref "U2") (pin "4") (pinfunction "VSS_4") (pintype "unspecified"))
      (node (ref "U8") (pin "4") (pinfunction "GND_4") (pintype "unspecified"))
    )
    (net (code "78") (name "AVCC_3V3") (class "Default")
      (node (ref "C52") (pin "1") (pinfunction "1_1") (pintype "input"))
      (node (ref "C53") (pin "2") (pinfunction "2_2") (pintype "input"))
      (node (ref "C54") (pin "2") (pinfunction "2_2") (pintype "input"))
      (node (ref "C55") (pin "2") (pinfunction "2_2") (pintype "input"))
      (node (ref "U2") (pin "6") (pinfunction "VOUT2_6") (pintype "unspecified"))
    )
    (net (code "79") (name "AVCC_5V") (class "Default")
      (node (ref "C12") (pin "2") (pinfunction "2_2") (pintype "input"))
      (node (ref "C40") (pin "1") (pinfunction "1_1") (pintype "input"))
      (node (ref "C41") (pin "2") (pinfunction "2_2") (pintype "input"))
      (node (ref "C42") (pin "2") (pinfunction "2_2") (pintype "input"))
      (node (ref "C43") (pin "2") (pinfunction "2_2") (pintype "input"))
      (node (ref "U17") (pin "47") (pinfunction "AVDD_47") (pintype "unspecified"))
      (node (ref "U6") (pin "6") (pinfunction "VOUT_6") (pintype "unspecified"))
      (node (ref "U8") (pin "2") (pinfunction "VIN_2") (pintype "unspecified"))
    )
    (net (code "80") (name "CH340_RXD") (class "Default")
      (node (ref "LED1") (pin "2") (pinfunction "C_2") (pintype "input"))
      (node (ref "U7") (pin "104") (pinfunction "IO_L1N_VREF_1_104") (pintype "unspecified"))
      (node (ref "U9") (pin "3") (pinfunction "RXD_3") (pintype "unspecified"))
    )
    (net (code "81") (name "CH340_TXD") (class "Default")
      (node (ref "D1") (pin "2") (pinfunction "A_2") (pintype "unspecified"))
      (node (ref "LED2") (pin "2") (pinfunction "C_2") (pintype "input"))
      (node (ref "U7") (pin "105") (pinfunction "IO_L1P_1_105") (pintype "unspecified"))
    )
    (net (code "82") (name "CRYSTAL_CLK0") (class "Default")
      (node (ref "U11") (pin "10") (pinfunction "CLK0_10") (pintype "unspecified"))
      (node (ref "U7") (pin "87") (pinfunction "IO_L42N_GCLK6_TRDY1_1_87") (pintype "unspecified"))
    )
    (net (code "83") (name "CRYSTAL_XA") (class "Default")
      (node (ref "C10") (pin "1") (pinfunction "1_1") (pintype "input"))
      (node (ref "U11") (pin "2") (pinfunction "XA_2") (pintype "unspecified"))
      (node (ref "X1") (pin "1") (pinfunction "OSC1_1") (pintype "unspecified"))
    )
    (net (code "84") (name "CRYSTAL_XB") (class "Default")
      (node (ref "C11") (pin "2") (pinfunction "2_2") (pintype "input"))
      (node (ref "U11") (pin "3") (pinfunction "XB_3") (pintype "unspecified"))
      (node (ref "X1") (pin "3") (pinfunction "OSC2_3") (pintype "unspecified"))
    )
    (net (code "85") (name "DAC_CLK1") (class "Default")
      (node (ref "U17") (pin "18") (pinfunction "CLK1/IQCLK_18") (pintype "unspecified"))
      (node (ref "U7") (pin "95") (pinfunction "IO_L40P_GCLK11_1_95") (pintype "unspecified"))
    )
    (net (code "86") (name "DAC_CLK2") (class "Default")
      (node (ref "U17") (pin "19") (pinfunction "CLK2/IQRESET_19") (pintype "unspecified"))
      (node (ref "U7") (pin "94") (pinfunction "IO_L40N_GCLK10_1_94") (pintype "unspecified"))
    )
    (net (code "87") (name "DAC_D0") (class "Default")
      (node (ref "U17") (pin "10") (pinfunction "DB0P1(LSB)_10") (pintype "unspecified"))
      (node (ref "U7") (pin "143") (pinfunction "IO_L1N_VREF_0_143") (pintype "unspecified"))
    )
    (net (code "88") (name "DAC_D1") (class "Default")
      (node (ref "U17") (pin "9") (pinfunction "DB1P1_9") (pintype "unspecified"))
      (node (ref "U7") (pin "142") (pinfunction "IO_L2P_0_142") (pintype "unspecified"))
    )
    (net (code "89") (name "DAC_D2") (class "Default")
      (node (ref "U17") (pin "8") (pinfunction "DB2P1_8") (pintype "unspecified"))
      (node (ref "U7") (pin "141") (pinfunction "IO_L2N_0_141") (pintype "unspecified"))
    )
    (net (code "90") (name "DAC_D3") (class "Default")
      (node (ref "U17") (pin "7") (pinfunction "DB3P1_7") (pintype "unspecified"))
      (node (ref "U7") (pin "140") (pinfunction "IO_L3P_0_140") (pintype "unspecified"))
    )
    (net (code "91") (name "DAC_D4") (class "Default")
      (node (ref "U17") (pin "6") (pinfunction "DB4P1_6") (pintype "unspecified"))
      (node (ref "U7") (pin "139") (pinfunction "IO_L3N_0_139") (pintype "unspecified"))
    )
    (net (code "92") (name "DAC_D5") (class "Default")
      (node (ref "U17") (pin "5") (pinfunction "DB5P1_5") (pintype "unspecified"))
      (node (ref "U7") (pin "138") (pinfunction "IO_L4P_0_138") (pintype "unspecified"))
    )
    (net (code "93") (name "DAC_D6") (class "Default")
      (node (ref "U17") (pin "4") (pinfunction "DB6P1_4") (pintype "unspecified"))
      (node (ref "U7") (pin "137") (pinfunction "IO_L4N_0_137") (pintype "unspecified"))
    )
    (net (code "94") (name "DAC_D7") (class "Default")
      (node (ref "U17") (pin "3") (pinfunction "DB7P1_3") (pintype "unspecified"))
      (node (ref "U7") (pin "134") (pinfunction "IO_L34P_GCLK19_0_134") (pintype "unspecified"))
    )
    (net (code "95") (name "DAC_D8") (class "Default")
      (node (ref "U17") (pin "2") (pinfunction "DB8P1_2") (pintype "unspecified"))
      (node (ref "U7") (pin "133") (pinfunction "IO_L34N_GCLK18_0_133") (pintype "unspecified"))
    )
    (net (code "96") (name "DAC_D9") (class "Default")
      (node (ref "U17") (pin "1") (pinfunction "DB9P1(MSB)_1") (pintype "unspecified"))
      (node (ref "U7") (pin "132") (pinfunction "IO_L35P_GCLK17_0_132") (pintype "unspecified"))
    )
    (net (code "97") (name "DAC_GAIN") (class "Default")
      (node (ref "C85") (pin "2") (pinfunction "2_2") (pintype "input"))
      (node (ref "U20") (pin "10") (pinfunction "GAIN_10") (pintype "unspecified"))
    )
    (net (code "98") (name "DAC_SLEEP") (class "Default")
      (node (ref "U17") (pin "37") (pinfunction "SLEEP_37") (pintype "unspecified"))
      (node (ref "U7") (pin "88") (pinfunction "IO_L42P_GCLK7_1_88") (pintype "unspecified"))
    )
    (net (code "99") (name "DAC_WRT1") (class "Default")
      (node (ref "U17") (pin "17") (pinfunction "WRT1/IQWRT_17") (pintype "unspecified"))
      (node (ref "U7") (pin "116") (pinfunction "IO_L64N_SCP4_0_116") (pintype "unspecified"))
    )
    (net (code "100") (name "DAC_WRT2") (class "Default")
      (node (ref "U17") (pin "20") (pinfunction "WRT2/IQSEL_20") (pintype "unspecified"))
      (node (ref "U7") (pin "115") (pinfunction "IO_L65P_SCP3_0_115") (pintype "unspecified"))
    )
    (net (code "101") (name "DAC_d0") (class "Default")
      (node (ref "U17") (pin "32") (pinfunction "DB0P2(LSB)_32") (pintype "unspecified"))
      (node (ref "U7") (pin "131") (pinfunction "IO_L35N_GCLK16_0_131") (pintype "unspecified"))
    )
    (net (code "102") (name "DAC_d1") (class "Default")
      (node (ref "U17") (pin "31") (pinfunction "DB1P2_31") (pintype "unspecified"))
      (node (ref "U7") (pin "127") (pinfunction "IO_L36P_GCLK15_0_127") (pintype "unspecified"))
    )
    (net (code "103") (name "DAC_d2") (class "Default")
      (node (ref "U17") (pin "30") (pinfunction "DB2P2_30") (pintype "unspecified"))
      (node (ref "U7") (pin "126") (pinfunction "IO_L36N_GCLK14_0_126") (pintype "unspecified"))
    )
    (net (code "104") (name "DAC_d3") (class "Default")
      (node (ref "U17") (pin "29") (pinfunction "DB3P2_29") (pintype "unspecified"))
      (node (ref "U7") (pin "124") (pinfunction "IO_L37P_GCLK13_0_124") (pintype "unspecified"))
    )
    (net (code "105") (name "DAC_d4") (class "Default")
      (node (ref "U17") (pin "28") (pinfunction "DB4P2_28") (pintype "unspecified"))
      (node (ref "U7") (pin "123") (pinfunction "IO_L37N_GCLK12_0_123") (pintype "unspecified"))
    )
    (net (code "106") (name "DAC_d5") (class "Default")
      (node (ref "U17") (pin "27") (pinfunction "DB5P2_27") (pintype "unspecified"))
      (node (ref "U7") (pin "121") (pinfunction "IO_L62P_0_121") (pintype "unspecified"))
    )
    (net (code "107") (name "DAC_d6") (class "Default")
      (node (ref "U17") (pin "26") (pinfunction "DB6P2_26") (pintype "unspecified"))
      (node (ref "U7") (pin "120") (pinfunction "IO_L62N_VREF_0_120") (pintype "unspecified"))
    )
    (net (code "108") (name "DAC_d7") (class "Default")
      (node (ref "U17") (pin "25") (pinfunction "DB7P2_25") (pintype "unspecified"))
      (node (ref "U7") (pin "119") (pinfunction "IO_L63P_SCP7_0_119") (pintype "unspecified"))
    )
    (net (code "109") (name "DAC_d8") (class "Default")
      (node (ref "U17") (pin "24") (pinfunction "DB8P2_24") (pintype "unspecified"))
      (node (ref "U7") (pin "118") (pinfunction "IO_L63N_SCP6_0_118") (pintype "unspecified"))
    )
    (net (code "110") (name "DAC_d9") (class "Default")
      (node (ref "U17") (pin "23") (pinfunction "DB9P2(MSB)_23") (pintype "unspecified"))
      (node (ref "U7") (pin "117") (pinfunction "IO_L64P_SCP5_0_117") (pintype "unspecified"))
    )
    (net (code "111") (name "DGND") (class "Default")
      (node (ref "C20") (pin "1") (pinfunction "1_1") (pintype "input"))
      (node (ref "C21") (pin "2") (pinfunction "2_2") (pintype "unspecified"))
      (node (ref "C60") (pin "1") (pinfunction "1_1") (pintype "input"))
      (node (ref "C61") (pin "2") (pinfunction "2_2") (pintype "input"))
      (node (ref "C62") (pin "1") (pinfunction "1_1") (pintype "input"))
      (node (ref "C63") (pin "2") (pinfunction "2_2") (pintype "input"))
      (node (ref "C64") (pin "2") (pinfunction "2_2") (pintype "input"))
      (node (ref "C66") (pin "1") (pinfunction "1_1") (pintype "input"))
      (node (ref "C73") (pin "1") (pinfunction "1_1") (pintype "input"))
      (node (ref "C80") (pin "1") (pinfunction "1_1") (pintype "input"))
      (node (ref "C81") (pin "1") (pinfunction "1_1") (pintype "input"))
      (node (ref "C82") (pin "1") (pinfunction "1_1") (pintype "input"))
      (node (ref "C85") (pin "1") (pinfunction "1_1") (pintype "input"))
      (node (ref "C86") (pin "2") (pinfunction "2_2") (pintype "input"))
      (node (ref "C87") (pin "2") (pinfunction "2_2") (pintype "input"))
      (node (ref "D4") (pin "1") (pinfunction "1_1") (pintype "input"))
      (node (ref "D4") (pin "2") (pinfunction "2_2") (pintype "input"))
      (node (ref "L1") (pin "2") (pinfunction "2_2") (pintype "unspecified"))
      (node (ref "R10") (pin "2") (pinfunction "2_2") (pintype "unspecified"))
      (node (ref "R11") (pin "1") (pinfunction "1_1") (pintype "unspecified"))
      (node (ref "RF1") (pin "1") (pinfunction "1_1") (pintype "unspecified"))
      (node (ref "RF1") (pin "2") (pinfunction "2_2") (pintype "unspecified"))
      (node (ref "RF1") (pin "3") (pinfunction "3_3") (pintype "unspecified"))
      (node (ref "RF1") (pin "4") (pinfunction "4_4") (pintype "unspecified"))
      (node (ref "RF2") (pin "1") (pinfunction "1_1") (pintype "unspecified"))
      (node (ref "RF2") (pin "2") (pinfunction "2_2") (pintype "unspecified"))
      (node (ref "RF2") (pin "3") (pinfunction "3_3") (pintype "unspecified"))
      (node (ref "RF2") (pin "4") (pinfunction "4_4") (pintype "unspecified"))
      (node (ref "U12") (pin "4") (pinfunction "VSS_4") (pintype "unspecified"))
      (node (ref "U17") (pin "15") (pinfunction "DCOM1_15") (pintype "unspecified"))
      (node (ref "U17") (pin "21") (pinfunction "DCOM2_21") (pintype "unspecified"))
      (node (ref "U19") (pin "A1") (pinfunction "GND_A1") (pintype "unspecified"))
      (node (ref "U19") (pin "A4") (pinfunction "VSS_A4") (pintype "unspecified"))
      (node (ref "U19") (pin "B2") (pinfunction "VL2_B2") (pintype "unspecified"))
      (node (ref "U19") (pin "B8") (pinfunction "VL1_B8") (pintype "unspecified"))
      (node (ref "U19") (pin "F7") (pinfunction "VL3_F7") (pintype "unspecified"))
      (node (ref "U19") (pin "P1") (pinfunction "SP2_P1") (pintype "unspecified"))
      (node (ref "U19") (pin "P4") (pinfunction "SN2_P4") (pintype "unspecified"))
      (node (ref "U20") (pin "17") (pinfunction "COMM_17") (pintype "unspecified"))
      (node (ref "U20") (pin "20") (pinfunction "COMM_20") (pintype "unspecified"))
      (node (ref "U20") (pin "6") (pinfunction "COML_6") (pintype "unspecified"))
      (node (ref "U20") (pin "9") (pinfunction "MODE_9") (pintype "unspecified"))
      (node (ref "U9") (pin "1") (pinfunction "GND_1") (pintype "unspecified"))
    )
    (net (code "112") (name "DVCC_1V2") (class "Default")
      (node (ref "C67") (pin "1") (pinfunction "1_1") (pintype "input"))
      (node (ref "C68") (pin "2") (pinfunction "2_2") (pintype "input"))
      (node (ref "C69") (pin "2") (pinfunction "2_2") (pintype "input"))
      (node (ref "C70") (pin "2") (pinfunction "2_2") (pintype "input"))
      (node (ref "C86") (pin "1") (pinfunction "1_1") (pintype "input"))
      (node (ref "C87") (pin "1") (pinfunction "1_1") (pintype "input"))
      (node (ref "U12") (pin "5") (pinfunction "VOUT1_5") (pintype "unspecified"))
      (node (ref "U20") (pin "11") (pinfunction "VCM_11") (pintype "unspecified"))
    )
    (net (code "113") (name "DVCC_3V3") (class "Default")
      (node (ref "C56") (pin "1") (pinfunction "1_1") (pintype "input"))
      (node (ref "C57") (pin "2") (pinfunction "2_2") (pintype "input"))
      (node (ref "C58") (pin "2") (pinfunction "2_2") (pintype "input"))
      (node (ref "C59") (pin "2") (pinfunction "2_2") (pintype "input"))
      (node (ref "C81") (pin "2") (pinfunction "2_2") (pintype "input"))
      (node (ref "R40") (pin "1") (pinfunction "1_1") (pintype "input"))
      (node (ref "R44") (pin "1") (pinfunction "1_1") (pintype "input"))
      (node (ref "U12") (pin "6") (pinfunction "VOUT2_6") (pintype "unspecified"))
      (node (ref "U17") (pin "22") (pinfunction "DVDD2_22") (pintype "unspecified"))
      (node (ref "U19") (pin "A9") (pinfunction "PE_A9") (pintype "unspecified"))
    )
    (net (code "114") (name "DVCC_5V") (class "Default")
      (node (ref "C44") (pin "1") (pinfunction "1_1") (pintype "input"))
      (node (ref "C45") (pin "2") (pinfunction "2_2") (pintype "input"))
      (node (ref "C46") (pin "2") (pinfunction "2_2") (pintype "input"))
      (node (ref "C47") (pin "2") (pinfunction "2_2") (pintype "input"))
      (node (ref "C82") (pin "2") (pinfunction "2_2") (pintype "input"))
      (node (ref "L1") (pin "1") (pinfunction "1_1") (pintype "unspecified"))
      (node (ref "L2") (pin "2") (pinfunction "2_2") (pintype "unspecified"))
      (node (ref "U10") (pin "6") (pinfunction "VOUT_6") (pintype "unspecified"))
      (node (ref "U17") (pin "16") (pinfunction "DVDD1_16") (pintype "unspecified"))
      (node (ref "U19") (pin "A6") (pinfunction "VDD_A6") (pintype "unspecified"))
      (node (ref "U19") (pin "F4") (pinfunction "VH_F4") (pintype "unspecified"))
    )
    (net (code "115") (name "FLASH_CLK") (class "Default")
      (node (ref "R4") (pin "1") (pinfunction "1_1") (pintype "unspecified"))
      (node (ref "U4") (pin "6") (pinfunction "CLK_6") (pintype "unspecified"))
      (node (ref "U7") (pin "70") (pinfunction "IO_L1P_CCLK_2_70") (pintype "unspecified"))
    )
    (net (code "116") (name "FLASH_CS") (class "Default")
      (node (ref "R1") (pin "1") (pinfunction "1_1") (pintype "unspecified"))
      (node (ref "U4") (pin "1") (pinfunction "CS#_1") (pintype "unspecified"))
      (node (ref "U7") (pin "38") (pinfunction "IO_L65N_CSO_B_2_38") (pintype "unspecified"))
    )
    (net (code "117") (name "FLASH_MISO") (class "Default")
      (node (ref "U4") (pin "2") (pinfunction "DO(IO1)_2") (pintype "unspecified"))
      (node (ref "U7") (pin "65") (pinfunction "IO_L3P_D0_DIN_MISO_MISO1_2_65") (pintype "unspecified"))
    )
    (net (code "118") (name "FLASH_MOSI") (class "Default")
      (node (ref "U4") (pin "5") (pinfunction "DI(IO0)_5") (pintype "unspecified"))
      (node (ref "U7") (pin "64") (pinfunction "IO_L3N_MOSI_CSI_B_MISO0_2_64") (pintype "unspecified"))
    )
    (net (code "119") (name "FPGA_DONE") (class "Default")
      (node (ref "R13") (pin "1") (pinfunction "1_1") (pintype "input"))
      (node (ref "R16") (pin "1") (pinfunction "1_1") (pintype "unspecified"))
      (node (ref "U7") (pin "71") (pinfunction "DONE_2_71") (pintype "unspecified"))
    )
    (net (code "120") (name "FPGA_HSWAP") (class "Default")
      (node (ref "R28") (pin "2") (pinfunction "2_2") (pintype "unspecified"))
      (node (ref "U7") (pin "144") (pinfunction "IO_L1P_HSWAPEN_0_144") (pintype "unspecified"))
    )
    (net (code "121") (name "FPGA_INIT") (class "Default")
      (node (ref "R26") (pin "2") (pinfunction "2_2") (pintype "unspecified"))
      (node (ref "U7") (pin "39") (pinfunction "IO_L65P_INIT_B_2_39") (pintype "unspecified"))
    )
    (net (code "122") (name "FPGA_M0") (class "Default")
      (node (ref "R22") (pin "1") (pinfunction "1_1") (pintype "unspecified"))
      (node (ref "U7") (pin "69") (pinfunction "IO_L1N_M0_CMPMISO_2_69") (pintype "unspecified"))
    )
    (net (code "123") (name "FPGA_M1") (class "Default")
      (node (ref "R27") (pin "1") (pinfunction "1_1") (pintype "input"))
      (node (ref "U7") (pin "60") (pinfunction "IO_L13P_M1_2_60") (pintype "unspecified"))
    )
    (net (code "124") (name "FPGA_PROG_B") (class "Default")
      (node (ref "C51") (pin "2") (pinfunction "2_2") (pintype "input"))
      (node (ref "R29") (pin "1") (pinfunction "1_1") (pintype "unspecified"))
      (node (ref "R30") (pin "1") (pinfunction "1_1") (pintype "input"))
      (node (ref "U7") (pin "37") (pinfunction "PROGRAM_B_2_37") (pintype "unspecified"))
    )
    (net (code "125") (name "FPGA_RES") (class "Default")
      (node (ref "C39") (pin "2") (pinfunction "2_2") (pintype "input"))
      (node (ref "R19") (pin "1") (pinfunction "1_1") (pintype "unspecified"))
      (node (ref "R23") (pin "1") (pinfunction "1_1") (pintype "input"))
      (node (ref "U7") (pin "27") (pinfunction "IO_L37P_3_27") (pintype "unspecified"))
    )
    (net (code "126") (name "FPGA_SCL") (class "Default")
      (node (ref "R6") (pin "1") (pinfunction "1_1") (pintype "unspecified"))
      (node (ref "R8") (pin "2") (pinfunction "2_2") (pintype "unspecified"))
      (node (ref "U11") (pin "4") (pinfunction "SCL_4") (pintype "unspecified"))
      (node (ref "U5") (pin "1") (pinfunction "SCL_1") (pintype "unspecified"))
      (node (ref "U7") (pin "112") (pinfunction "IO_L66P_SCP1_0_112") (pintype "unspecified"))
    )
    (net (code "127") (name "FPGA_SDA") (class "Default")
      (node (ref "R5") (pin "1") (pinfunction "1_1") (pintype "unspecified"))
      (node (ref "R7") (pin "2") (pinfunction "2_2") (pintype "unspecified"))
      (node (ref "U11") (pin "5") (pinfunction "SDA_5") (pintype "unspecified"))
      (node (ref "U5") (pin "3") (pinfunction "SDA_3") (pintype "unspecified"))
      (node (ref "U7") (pin "111") (pinfunction "IO_L66N_SCP0_0_111") (pintype "unspecified"))
    )
    (net (code "128") (name "GND") (class "Default")
      (node (ref "C1") (pin "1") (pinfunction "1_1") (pintype "input"))
      (node (ref "C10") (pin "2") (pinfunction "2_2") (pintype "input"))
      (node (ref "C11") (pin "1") (pinfunction "1_1") (pintype "input"))
      (node (ref "C13") (pin "2") (pinfunction "2_2") (pintype "input"))
      (node (ref "C16") (pin "2") (pinfunction "2_2") (pintype "input"))
      (node (ref "C17") (pin "1") (pinfunction "1_1") (pintype "input"))
      (node (ref "C18") (pin "1") (pinfunction "1_1") (pintype "input"))
      (node (ref "C2") (pin "1") (pinfunction "1_1") (pintype "input"))
      (node (ref "C22") (pin "1") (pinfunction "1_1") (pintype "input"))
      (node (ref "C23") (pin "2") (pinfunction "2_2") (pintype "input"))
      (node (ref "C24") (pin "1") (pinfunction "1_1") (pintype "input"))
      (node (ref "C25") (pin "1") (pinfunction "1_1") (pintype "input"))
      (node (ref "C26") (pin "1") (pinfunction "1_1") (pintype "input"))
      (node (ref "C27") (pin "2") (pinfunction "2_2") (pintype "input"))
      (node (ref "C28") (pin "1") (pinfunction "1_1") (pintype "input"))
      (node (ref "C29") (pin "1") (pinfunction "1_1") (pintype "input"))
      (node (ref "C3") (pin "2") (pinfunction "2_2") (pintype "unspecified"))
      (node (ref "C30") (pin "1") (pinfunction "1_1") (pintype "input"))
      (node (ref "C32") (pin "2") (pinfunction "2_2") (pintype "input"))
      (node (ref "C33") (pin "1") (pinfunction "1_1") (pintype "input"))
      (node (ref "C34") (pin "1") (pinfunction "1_1") (pintype "input"))
      (node (ref "C35") (pin "1") (pinfunction "1_1") (pintype "input"))
      (node (ref "C39") (pin "1") (pinfunction "1_1") (pintype "input"))
      (node (ref "C44") (pin "2") (pinfunction "2_2") (pintype "input"))
      (node (ref "C45") (pin "1") (pinfunction "1_1") (pintype "input"))
      (node (ref "C46") (pin "1") (pinfunction "1_1") (pintype "input"))
      (node (ref "C47") (pin "1") (pinfunction "1_1") (pintype "input"))
      (node (ref "C51") (pin "1") (pinfunction "1_1") (pintype "input"))
      (node (ref "C56") (pin "2") (pinfunction "2_2") (pintype "input"))
      (node (ref "C57") (pin "1") (pinfunction "1_1") (pintype "input"))
      (node (ref "C58") (pin "1") (pinfunction "1_1") (pintype "input"))
      (node (ref "C59") (pin "1") (pinfunction "1_1") (pintype "input"))
      (node (ref "C6") (pin "1") (pinfunction "1_1") (pintype "input"))
      (node (ref "C67") (pin "2") (pinfunction "2_2") (pintype "input"))
      (node (ref "C68") (pin "1") (pinfunction "1_1") (pintype "input"))
      (node (ref "C69") (pin "1") (pinfunction "1_1") (pintype "input"))
      (node (ref "C7") (pin "1") (pinfunction "1_1") (pintype "input"))
      (node (ref "C70") (pin "1") (pinfunction "1_1") (pintype "input"))
      (node (ref "C8") (pin "1") (pinfunction "1_1") (pintype "unspecified"))
      (node (ref "H1") (pin "2") (pinfunction "2_2") (pintype "input"))
      (node (ref "H2") (pin "1") (pinfunction "1_1") (pintype "unspecified"))
      (node (ref "KEY1") (pin "2") (pinfunction "2_2") (pintype "unspecified"))
      (node (ref "KEY2") (pin "2") (pinfunction "2_2") (pintype "unspecified"))
      (node (ref "R10") (pin "1") (pinfunction "1_1") (pintype "unspecified"))
      (node (ref "R16") (pin "2") (pinfunction "2_2") (pintype "unspecified"))
      (node (ref "R27") (pin "2") (pinfunction "2_2") (pintype "input"))
      (node (ref "R28") (pin "1") (pinfunction "1_1") (pintype "unspecified"))
      (node (ref "R9") (pin "2") (pinfunction "2_2") (pintype "unspecified"))
      (node (ref "U1") (pin "4") (pinfunction "VSS_4") (pintype "unspecified"))
      (node (ref "U10") (pin "8") (pinfunction "GND_8") (pintype "unspecified"))
      (node (ref "U10") (pin "9") (pinfunction "GND_9") (pintype "unspecified"))
      (node (ref "U11") (pin "8") (pinfunction "GND_8") (pintype "unspecified"))
      (node (ref "U13") (pin "5") (pinfunction "GND_5") (pintype "unspecified"))
      (node (ref "U14") (pin "2") (pinfunction "GND_2") (pintype "unspecified"))
      (node (ref "U14") (pin "9") (pinfunction "PAD_9") (pintype "unspecified"))
      (node (ref "U15") (pin "5") (pinfunction "GND_5") (pintype "unspecified"))
      (node (ref "U3") (pin "12") (pinfunction "GND_12") (pintype "unspecified"))
      (node (ref "U3") (pin "34") (pinfunction "GND_34") (pintype "unspecified"))
      (node (ref "U4") (pin "4") (pinfunction "GND_4") (pintype "unspecified"))
      (node (ref "U5") (pin "2") (pinfunction "GND_2") (pintype "unspecified"))
      (node (ref "U5") (pin "5") (pinfunction "WP_5") (pintype "unspecified"))
      (node (ref "U6") (pin "8") (pinfunction "GND_8") (pintype "unspecified"))
      (node (ref "U6") (pin "9") (pinfunction "GND_9") (pintype "unspecified"))
      (node (ref "U7") (pin "108") (pinfunction "GND_J_108") (pintype "passive"))
      (node (ref "U7") (pin "113") (pinfunction "GND_K_113") (pintype "passive"))
      (node (ref "U7") (pin "13") (pinfunction "GND_B_13") (pintype "passive"))
      (node (ref "U7") (pin "130") (pinfunction "GND_L_130") (pintype "passive"))
      (node (ref "U7") (pin "136") (pinfunction "GND_M_136") (pintype "passive"))
      (node (ref "U7") (pin "25") (pinfunction "GND_C_25") (pintype "unspecified"))
      (node (ref "U7") (pin "3") (pinfunction "GND_A_3") (pintype "passive"))
      (node (ref "U7") (pin "49") (pinfunction "GND_D_49") (pintype "passive"))
      (node (ref "U7") (pin "54") (pinfunction "GND_E_54") (pintype "passive"))
      (node (ref "U7") (pin "68") (pinfunction "GND_F_68") (pintype "passive"))
      (node (ref "U7") (pin "77") (pinfunction "GND_G_77") (pintype "passive"))
      (node (ref "U7") (pin "91") (pinfunction "GND_H_91") (pintype "passive"))
      (node (ref "U7") (pin "96") (pinfunction "GND_I_96") (pintype "passive"))
      (node (ref "USB1") (pin "5") (pinfunction "GND_5") (pintype "bidirectional"))
      (node (ref "X1") (pin "2") (pinfunction "GND_2") (pintype "unspecified"))
      (node (ref "X1") (pin "4") (pinfunction "GND_4") (pintype "unspecified"))
    )
    (net (code "129") (name "HILO") (class "Default")
      (node (ref "U20") (pin "13") (pinfunction "HILO_13") (pintype "unspecified"))
      (node (ref "U7") (pin "73") (pinfunction "SUSPEND_73") (pintype "unspecified"))
    )
    (net (code "130") (name "HV_RX") (class "Default")
      (node (ref "D4") (pin "3") (pinfunction "3_3") (pintype "input"))
      (node (ref "L5") (pin "1") (pinfunction "1_1") (pintype "unspecified"))
      (node (ref "U19") (pin "G4") (pinfunction "RX_G4") (pintype "unspecified"))
    )
    (net (code "131") (name "HV_XDCR") (class "Default")
      (node (ref "R33") (pin "1") (pinfunction "1_1") (pintype "unspecified"))
      (node (ref "U19") (pin "P5") (pinfunction "XDCR_P5") (pintype "unspecified"))
    )
    (net (code "132") (name "Net-(C71-Pad2)") (class "Default")
      (node (ref "C71") (pin "2") (pinfunction "2_2") (pintype "input"))
      (node (ref "C72") (pin "2") (pinfunction "2_2") (pintype "input"))
      (node (ref "L2") (pin "1") (pinfunction "1_1") (pintype "unspecified"))
    )
    (net (code "133") (name "Net-(C74-Pad1)") (class "Default")
      (node (ref "C74") (pin "1") (pinfunction "1_1") (pintype "input"))
      (node (ref "R37") (pin "1") (pinfunction "1_1") (pintype "unspecified"))
    )
    (net (code "134") (name "Net-(C74-Pad2)") (class "Default")
      (node (ref "C74") (pin "2") (pinfunction "2_2") (pintype "input"))
      (node (ref "L3") (pin "2") (pinfunction "2_2") (pintype "unspecified"))
      (node (ref "R36") (pin "2") (pinfunction "2_2") (pintype "unspecified"))
    )
    (net (code "135") (name "Net-(C75-Pad2)") (class "Default")
      (node (ref "C75") (pin "2") (pinfunction "2_2") (pintype "input"))
      (node (ref "R35") (pin "1") (pinfunction "1_1") (pintype "unspecified"))
    )
    (net (code "136") (name "Net-(C78-Pad1)") (class "Default")
      (node (ref "C78") (pin "1") (pinfunction "1_1") (pintype "input"))
      (node (ref "L5") (pin "2") (pinfunction "2_2") (pintype "unspecified"))
    )
    (net (code "137") (name "Net-(C79-Pad1)") (class "Default")
      (node (ref "C79") (pin "1") (pinfunction "1_1") (pintype "input"))
      (node (ref "R42") (pin "1") (pinfunction "1_1") (pintype "unspecified"))
    )
    (net (code "138") (name "Net-(C79-Pad2)") (class "Default")
      (node (ref "C79") (pin "2") (pinfunction "2_2") (pintype "input"))
      (node (ref "L4") (pin "2") (pinfunction "2_2") (pintype "unspecified"))
      (node (ref "R41") (pin "2") (pinfunction "2_2") (pintype "unspecified"))
    )
    (net (code "139") (name "Net-(C83-Pad1)") (class "Default")
      (node (ref "C83") (pin "1") (pinfunction "1_1") (pintype "input"))
      (node (ref "C84") (pin "1") (pinfunction "1_1") (pintype "input"))
      (node (ref "R45") (pin "1") (pinfunction "1_1") (pintype "input"))
    )
    (net (code "140") (name "Net-(D1-C)") (class "Default")
      (node (ref "D1") (pin "1") (pinfunction "C_1") (pintype "unspecified"))
      (node (ref "U9") (pin "2") (pinfunction "TXD_2") (pintype "unspecified"))
    )
    (net (code "141") (name "Net-(D2-Pad3)") (class "Default")
      (node (ref "D2") (pin "3") (pinfunction "3_3") (pintype "input"))
      (node (ref "D3") (pin "3") (pinfunction "3_3") (pintype "input"))
      (node (ref "R33") (pin "2") (pinfunction "2_2") (pintype "unspecified"))
      (node (ref "R34") (pin "2") (pinfunction "2_2") (pintype "unspecified"))
      (node (ref "RF1") (pin "5") (pinfunction "5_5") (pintype "unspecified"))
    )
    (net (code "142") (name "Net-(KEY1-Pad1)") (class "Default")
      (node (ref "KEY1") (pin "1") (pinfunction "1_1") (pintype "unspecified"))
      (node (ref "R23") (pin "2") (pinfunction "2_2") (pintype "input"))
    )
    (net (code "143") (name "Net-(KEY2-Pad1)") (class "Default")
      (node (ref "KEY2") (pin "1") (pinfunction "1_1") (pintype "unspecified"))
      (node (ref "R30") (pin "2") (pinfunction "2_2") (pintype "input"))
    )
    (net (code "144") (name "Net-(LED1-A)") (class "Default")
      (node (ref "LED1") (pin "1") (pinfunction "A_1") (pintype "input"))
      (node (ref "R40") (pin "2") (pinfunction "2_2") (pintype "input"))
    )
    (net (code "145") (name "Net-(LED2-A)") (class "Default")
      (node (ref "LED2") (pin "1") (pinfunction "A_1") (pintype "input"))
      (node (ref "R44") (pin "2") (pinfunction "2_2") (pintype "input"))
    )
    (net (code "146") (name "Net-(R34-Pad1)") (class "Default")
      (node (ref "R34") (pin "1") (pinfunction "1_1") (pintype "unspecified"))
      (node (ref "RF2") (pin "5") (pinfunction "5_5") (pintype "unspecified"))
    )
    (net (code "147") (name "Net-(R43-Pad2)") (class "Default")
      (node (ref "R43") (pin "2") (pinfunction "2_2") (pintype "unspecified"))
      (node (ref "R45") (pin "2") (pinfunction "2_2") (pintype "input"))
    )
    (net (code "148") (name "Net-(U4-HOLD#orRESET#(IO3))") (class "Default")
      (node (ref "R3") (pin "1") (pinfunction "1_1") (pintype "unspecified"))
      (node (ref "U4") (pin "7") (pinfunction "HOLD#orRESET#(IO3)_7") (pintype "unspecified"))
    )
    (net (code "149") (name "Net-(U4-WP#(IO2))") (class "Default")
      (node (ref "R2") (pin "1") (pinfunction "1_1") (pintype "unspecified"))
      (node (ref "U4") (pin "3") (pinfunction "WP#(IO2)_3") (pintype "unspecified"))
    )
    (net (code "150") (name "Net-(U6-C1+)") (class "Default")
      (node (ref "C9") (pin "1") (pinfunction "1_1") (pintype "input"))
      (node (ref "U6") (pin "3") (pinfunction "C1+_3") (pintype "unspecified"))
    )
    (net (code "151") (name "Net-(U6-C1–)") (class "Default")
      (node (ref "C9") (pin "2") (pinfunction "2_2") (pintype "input"))
      (node (ref "U6") (pin "2") (pinfunction "C1–_2") (pintype "unspecified"))
    )
    (net (code "152") (name "Net-(U9-V3)") (class "Default")
      (node (ref "C16") (pin "1") (pinfunction "1_1") (pintype "input"))
      (node (ref "U9") (pin "4") (pinfunction "V3_4") (pintype "unspecified"))
    )
    (net (code "153") (name "Net-(U10-C1+)") (class "Default")
      (node (ref "C15") (pin "1") (pinfunction "1_1") (pintype "input"))
      (node (ref "U10") (pin "3") (pinfunction "C1+_3") (pintype "unspecified"))
    )
    (net (code "154") (name "Net-(U10-C1–)") (class "Default")
      (node (ref "C15") (pin "2") (pinfunction "2_2") (pintype "input"))
      (node (ref "U10") (pin "2") (pinfunction "C1–_2") (pintype "unspecified"))
    )
    (net (code "155") (name "Net-(U14-C1+)") (class "Default")
      (node (ref "C19") (pin "1") (pinfunction "1_1") (pintype "input"))
      (node (ref "U14") (pin "8") (pinfunction "C1+_8") (pintype "unspecified"))
    )
    (net (code "156") (name "Net-(U14-C1-)") (class "Default")
      (node (ref "C19") (pin "2") (pinfunction "2_2") (pintype "input"))
      (node (ref "U14") (pin "7") (pinfunction "C1-_7") (pintype "unspecified"))
    )
    (net (code "157") (name "Net-(U14-CPOUT)") (class "Default")
      (node (ref "C22") (pin "2") (pinfunction "2_2") (pintype "input"))
      (node (ref "U14") (pin "3") (pinfunction "CPOUT_3") (pintype "unspecified"))
    )
    (net (code "158") (name "Net-(U14-VFB)") (class "Default")
      (node (ref "R12") (pin "2") (pinfunction "2_2") (pintype "unspecified"))
      (node (ref "R9") (pin "1") (pinfunction "1_1") (pintype "unspecified"))
      (node (ref "U14") (pin "5") (pinfunction "VFB_5") (pintype "unspecified"))
    )
    (net (code "159") (name "Net-(U16-OUT+)") (class "Default")
      (node (ref "R24") (pin "2") (pinfunction "2_2") (pintype "unspecified"))
      (node (ref "U16") (pin "4") (pinfunction "OUT+_4") (pintype "unspecified"))
    )
    (net (code "160") (name "Net-(U16-OUT–)") (class "Default")
      (node (ref "R25") (pin "1") (pinfunction "1_1") (pintype "unspecified"))
      (node (ref "U16") (pin "5") (pinfunction "OUT–_5") (pintype "unspecified"))
    )
    (net (code "161") (name "Net-(U18-OUT+)") (class "Default")
      (node (ref "R31") (pin "2") (pinfunction "2_2") (pintype "unspecified"))
      (node (ref "U18") (pin "4") (pinfunction "OUT+_4") (pintype "unspecified"))
    )
    (net (code "162") (name "Net-(U18-OUT–)") (class "Default")
      (node (ref "R32") (pin "1") (pinfunction "1_1") (pintype "unspecified"))
      (node (ref "U18") (pin "5") (pinfunction "OUT–_5") (pintype "unspecified"))
    )
    (net (code "163") (name "Net-(U19-DN1)") (class "Default")
      (node (ref "D2") (pin "2") (pinfunction "2_2") (pintype "input"))
      (node (ref "U19") (pin "P8") (pinfunction "DN1_P8") (pintype "unspecified"))
    )
    (net (code "164") (name "Net-(U19-DN2)") (class "Default")
      (node (ref "D3") (pin "2") (pinfunction "2_2") (pintype "input"))
      (node (ref "U19") (pin "P3") (pinfunction "DN2_P3") (pintype "unspecified"))
    )
    (net (code "165") (name "Net-(U19-DP1)") (class "Default")
      (node (ref "D2") (pin "1") (pinfunction "1_1") (pintype "input"))
      (node (ref "U19") (pin "P7") (pinfunction "DP1_P7") (pintype "unspecified"))
    )
    (net (code "166") (name "Net-(U19-DP2)") (class "Default")
      (node (ref "D3") (pin "1") (pinfunction "1_1") (pintype "input"))
      (node (ref "U19") (pin "P2") (pinfunction "DP2_P2") (pintype "unspecified"))
    )
    (net (code "167") (name "Net-(U20-ENBL)") (class "Default")
      (node (ref "R38") (pin "1") (pinfunction "1_1") (pintype "unspecified"))
      (node (ref "U20") (pin "19") (pinfunction "ENBL_19") (pintype "unspecified"))
    )
    (net (code "168") (name "Net-(U20-ENBV)") (class "Default")
      (node (ref "R39") (pin "1") (pinfunction "1_1") (pintype "unspecified"))
      (node (ref "U20") (pin "18") (pinfunction "ENBV_18") (pintype "unspecified"))
    )
    (net (code "169") (name "Net-(U20-INH)") (class "Default")
      (node (ref "C75") (pin "1") (pinfunction "1_1") (pintype "input"))
      (node (ref "C78") (pin "2") (pinfunction "2_2") (pintype "input"))
      (node (ref "C80") (pin "2") (pinfunction "2_2") (pintype "input"))
      (node (ref "U20") (pin "2") (pinfunction "INH_2") (pintype "unspecified"))
    )
    (net (code "170") (name "Net-(U20-LMD)") (class "Default")
      (node (ref "C64") (pin "1") (pinfunction "1_1") (pintype "input"))
      (node (ref "U20") (pin "1") (pinfunction "LMD_1") (pintype "unspecified"))
    )
    (net (code "171") (name "Net-(U20-LOP)") (class "Default")
      (node (ref "C77") (pin "2") (pinfunction "2_2") (pintype "input"))
      (node (ref "U20") (pin "5") (pinfunction "LOP_5") (pintype "unspecified"))
    )
    (net (code "172") (name "Net-(U20-RCLMP)") (class "Default")
      (node (ref "C83") (pin "2") (pinfunction "2_2") (pintype "input"))
      (node (ref "C84") (pin "2") (pinfunction "2_2") (pintype "input"))
      (node (ref "R43") (pin "1") (pinfunction "1_1") (pintype "unspecified"))
      (node (ref "U20") (pin "12") (pinfunction "RCLMP_12") (pintype "unspecified"))
    )
    (net (code "173") (name "Net-(U20-VIN)") (class "Default")
      (node (ref "C65") (pin "2") (pinfunction "2_2") (pintype "input"))
      (node (ref "U20") (pin "8") (pinfunction "VIN_8") (pintype "unspecified"))
    )
    (net (code "174") (name "Net-(U20-VIP)") (class "Default")
      (node (ref "C77") (pin "1") (pinfunction "1_1") (pintype "input"))
      (node (ref "U20") (pin "7") (pinfunction "VIP_7") (pintype "unspecified"))
    )
    (net (code "175") (name "Net-(U20-VOH)") (class "Default")
      (node (ref "L4") (pin "1") (pinfunction "1_1") (pintype "unspecified"))
      (node (ref "R41") (pin "1") (pinfunction "1_1") (pintype "unspecified"))
      (node (ref "U20") (pin "15") (pinfunction "VOH_15") (pintype "unspecified"))
    )
    (net (code "176") (name "Net-(U20-VOL)") (class "Default")
      (node (ref "L3") (pin "1") (pinfunction "1_1") (pintype "unspecified"))
      (node (ref "R36") (pin "1") (pinfunction "1_1") (pintype "unspecified"))
      (node (ref "U20") (pin "16") (pinfunction "VOL_16") (pintype "unspecified"))
    )
    (net (code "177") (name "Net-(U20-VPOS)") (class "Default")
      (node (ref "C71") (pin "1") (pinfunction "1_1") (pintype "input"))
      (node (ref "C72") (pin "1") (pinfunction "1_1") (pintype "input"))
      (node (ref "R38") (pin "2") (pinfunction "2_2") (pintype "unspecified"))
      (node (ref "R39") (pin "2") (pinfunction "2_2") (pintype "unspecified"))
      (node (ref "U20") (pin "14") (pinfunction "VPOS_14") (pintype "unspecified"))
    )
    (net (code "178") (name "Net-(U20-VPSL)") (class "Default")
      (node (ref "C66") (pin "2") (pinfunction "2_2") (pintype "input"))
      (node (ref "C73") (pin "2") (pinfunction "2_2") (pintype "input"))
      (node (ref "U20") (pin "3") (pinfunction "VPSL_3") (pintype "unspecified"))
    )
    (net (code "179") (name "PDAMAP") (class "Default")
      (node (ref "U19") (pin "A2") (pinfunction "IND_A2") (pintype "unspecified"))
      (node (ref "U19") (pin "A3") (pinfunction "INC_A3") (pintype "unspecified"))
    )
    (net (code "180") (name "PHV") (class "Default")
      (node (ref "U19") (pin "A8") (pinfunction "INA_A8") (pintype "unspecified"))
      (node (ref "U7") (pin "6") (pinfunction "IO_L52P_3_6") (pintype "unspecified"))
    )
    (net (code "181") (name "PNHV") (class "Default")
      (node (ref "U19") (pin "A7") (pinfunction "INB_A7") (pintype "unspecified"))
      (node (ref "U7") (pin "5") (pinfunction "IO_L52N_3_5") (pintype "unspecified"))
    )
    (net (code "182") (name "TO_LON") (class "Default")
      (node (ref "C65") (pin "1") (pinfunction "1_1") (pintype "input"))
      (node (ref "R35") (pin "2") (pinfunction "2_2") (pintype "unspecified"))
      (node (ref "U20") (pin "4") (pinfunction "LON_4") (pintype "unspecified"))
    )
    (net (code "183") (name "USB_D+") (class "Default")
      (node (ref "U9") (pin "5") (pinfunction "D+_5") (pintype "unspecified"))
      (node (ref "USB1") (pin "3") (pinfunction "Data+_3") (pintype "input"))
    )
    (net (code "184") (name "USB_D-") (class "Default")
      (node (ref "U9") (pin "6") (pinfunction "D-_6") (pintype "unspecified"))
      (node (ref "USB1") (pin "2") (pinfunction "Data-_2") (pintype "input"))
    )
    (net (code "185") (name "USB_VBUS") (class "Default")
      (node (ref "C8") (pin "2") (pinfunction "2_2") (pintype "unspecified"))
      (node (ref "F1") (pin "1") (pinfunction "1_1") (pintype "unspecified"))
      (node (ref "H1") (pin "1") (pinfunction "1_1") (pintype "input"))
      (node (ref "USB1") (pin "1") (pinfunction "VBUS_1") (pintype "bidirectional"))
    )
    (net (code "186") (name "VGA_VOH") (class "Default")
      (node (ref "C76") (pin "1") (pinfunction "1_1") (pintype "input"))
      (node (ref "R42") (pin "2") (pinfunction "2_2") (pintype "unspecified"))
      (node (ref "U16") (pin "8") (pinfunction "IN_8") (pintype "unspecified"))
      (node (ref "U18") (pin "8") (pinfunction "IN_8") (pintype "unspecified"))
    )
    (net (code "187") (name "VGA_VOL") (class "Default")
      (node (ref "C76") (pin "2") (pinfunction "2_2") (pintype "input"))
      (node (ref "R37") (pin "2") (pinfunction "2_2") (pintype "unspecified"))
    )
    (net (code "188") (name "unconnected-(U1-PAD-Pad7)") (class "Default")
      (node (ref "U1") (pin "7") (pinfunction "PAD_7") (pintype "unspecified+no_connect"))
    )
    (net (code "189") (name "unconnected-(U2-PAD-Pad7)") (class "Default")
      (node (ref "U2") (pin "7") (pinfunction "PAD_7") (pintype "unspecified+no_connect"))
    )
    (net (code "190") (name "unconnected-(U2-VOUT1-Pad5)") (class "Default")
      (node (ref "U2") (pin "5") (pinfunction "VOUT1_5") (pintype "unspecified+no_connect"))
    )
    (net (code "191") (name "unconnected-(U7-CMPCS_B_2-Pad72)") (class "Default")
      (node (ref "U7") (pin "72") (pinfunction "CMPCS_B_2_72") (pintype "unspecified+no_connect"))
    )
    (net (code "192") (name "unconnected-(U8-DNC-Pad1)") (class "Default")
      (node (ref "U8") (pin "1") (pinfunction "DNC_1") (pintype "unspecified+no_connect"))
    )
    (net (code "193") (name "unconnected-(U8-DNC-Pad8)") (class "Default")
      (node (ref "U8") (pin "8") (pinfunction "DNC_8") (pintype "unspecified+no_connect"))
    )
    (net (code "194") (name "unconnected-(U8-NC-Pad7)") (class "Default")
      (node (ref "U8") (pin "7") (pinfunction "NC_7") (pintype "unspecified+no_connect"))
    )
    (net (code "195") (name "unconnected-(U8-TEMP-Pad3)") (class "Default")
      (node (ref "U8") (pin "3") (pinfunction "TEMP_3") (pintype "unspecified+no_connect"))
    )
    (net (code "196") (name "unconnected-(U8-TRIM{slash}NR-Pad5)") (class "Default")
      (node (ref "U8") (pin "5") (pinfunction "TRIM/NR_5") (pintype "unspecified+no_connect"))
    )
    (net (code "197") (name "unconnected-(U9-CTS#-Pad9)") (class "Default")
      (node (ref "U9") (pin "9") (pinfunction "CTS#_9") (pintype "unspecified+no_connect"))
    )
    (net (code "198") (name "unconnected-(U9-DCD#-Pad12)") (class "Default")
      (node (ref "U9") (pin "12") (pinfunction "DCD#_12") (pintype "unspecified+no_connect"))
    )
    (net (code "199") (name "unconnected-(U9-DSR#-Pad10)") (class "Default")
      (node (ref "U9") (pin "10") (pinfunction "DSR#_10") (pintype "unspecified+no_connect"))
    )
    (net (code "200") (name "unconnected-(U9-DTR#-Pad13)") (class "Default")
      (node (ref "U9") (pin "13") (pinfunction "DTR#_13") (pintype "unspecified+no_connect"))
    )
    (net (code "201") (name "unconnected-(U9-NC.-Pad7)") (class "Default")
      (node (ref "U9") (pin "7") (pinfunction "NC._7") (pintype "unspecified+no_connect"))
    )
    (net (code "202") (name "unconnected-(U9-NC.-Pad8)") (class "Default")
      (node (ref "U9") (pin "8") (pinfunction "NC._8") (pintype "unspecified+no_connect"))
    )
    (net (code "203") (name "unconnected-(U9-R232-Pad15)") (class "Default")
      (node (ref "U9") (pin "15") (pinfunction "R232_15") (pintype "unspecified+no_connect"))
    )
    (net (code "204") (name "unconnected-(U9-RI#-Pad11)") (class "Default")
      (node (ref "U9") (pin "11") (pinfunction "RI#_11") (pintype "unspecified+no_connect"))
    )
    (net (code "205") (name "unconnected-(U9-RTS#-Pad14)") (class "Default")
      (node (ref "U9") (pin "14") (pinfunction "RTS#_14") (pintype "unspecified+no_connect"))
    )
    (net (code "206") (name "unconnected-(U11-CLK1-Pad9)") (class "Default")
      (node (ref "U11") (pin "9") (pinfunction "CLK1_9") (pintype "unspecified+no_connect"))
    )
    (net (code "207") (name "unconnected-(U11-CLK2-Pad6)") (class "Default")
      (node (ref "U11") (pin "6") (pinfunction "CLK2_6") (pintype "unspecified+no_connect"))
    )
    (net (code "208") (name "unconnected-(U12-PAD-Pad7)") (class "Default")
      (node (ref "U12") (pin "7") (pinfunction "PAD_7") (pintype "unspecified+no_connect"))
    )
    (net (code "209") (name "unconnected-(U17-NC-Pad11)") (class "Default")
      (node (ref "U17") (pin "11") (pinfunction "NC_11") (pintype "unspecified+no_connect"))
    )
    (net (code "210") (name "unconnected-(U17-NC-Pad12)") (class "Default")
      (node (ref "U17") (pin "12") (pinfunction "NC_12") (pintype "unspecified+no_connect"))
    )
    (net (code "211") (name "unconnected-(U17-NC-Pad13)") (class "Default")
      (node (ref "U17") (pin "13") (pinfunction "NC_13") (pintype "unspecified+no_connect"))
    )
    (net (code "212") (name "unconnected-(U17-NC-Pad14)") (class "Default")
      (node (ref "U17") (pin "14") (pinfunction "NC_14") (pintype "unspecified+no_connect"))
    )
    (net (code "213") (name "unconnected-(U17-NC-Pad33)") (class "Default")
      (node (ref "U17") (pin "33") (pinfunction "NC_33") (pintype "unspecified+no_connect"))
    )
    (net (code "214") (name "unconnected-(U17-NC-Pad34)") (class "Default")
      (node (ref "U17") (pin "34") (pinfunction "NC_34") (pintype "unspecified+no_connect"))
    )
    (net (code "215") (name "unconnected-(U17-NC-Pad35)") (class "Default")
      (node (ref "U17") (pin "35") (pinfunction "NC_35") (pintype "unspecified+no_connect"))
    )
    (net (code "216") (name "unconnected-(U17-NC-Pad36)") (class "Default")
      (node (ref "U17") (pin "36") (pinfunction "NC_36") (pintype "unspecified+no_connect"))
    )
    (net (code "217") (name "unconnected-(USB1-ID-Pad4)") (class "Default")
      (node (ref "USB1") (pin "4") (pinfunction "ID_4") (pintype "bidirectional+no_connect"))
    )
    (net (code "218") (name "unconnected-(USB1-Pad6)") (class "Default")
      (node (ref "USB1") (pin "6") (pintype "unspecified+no_connect"))
    )
  )
)
